# OBCv4_24.net
KiCad netlist of a schematic drawn in EAGLE
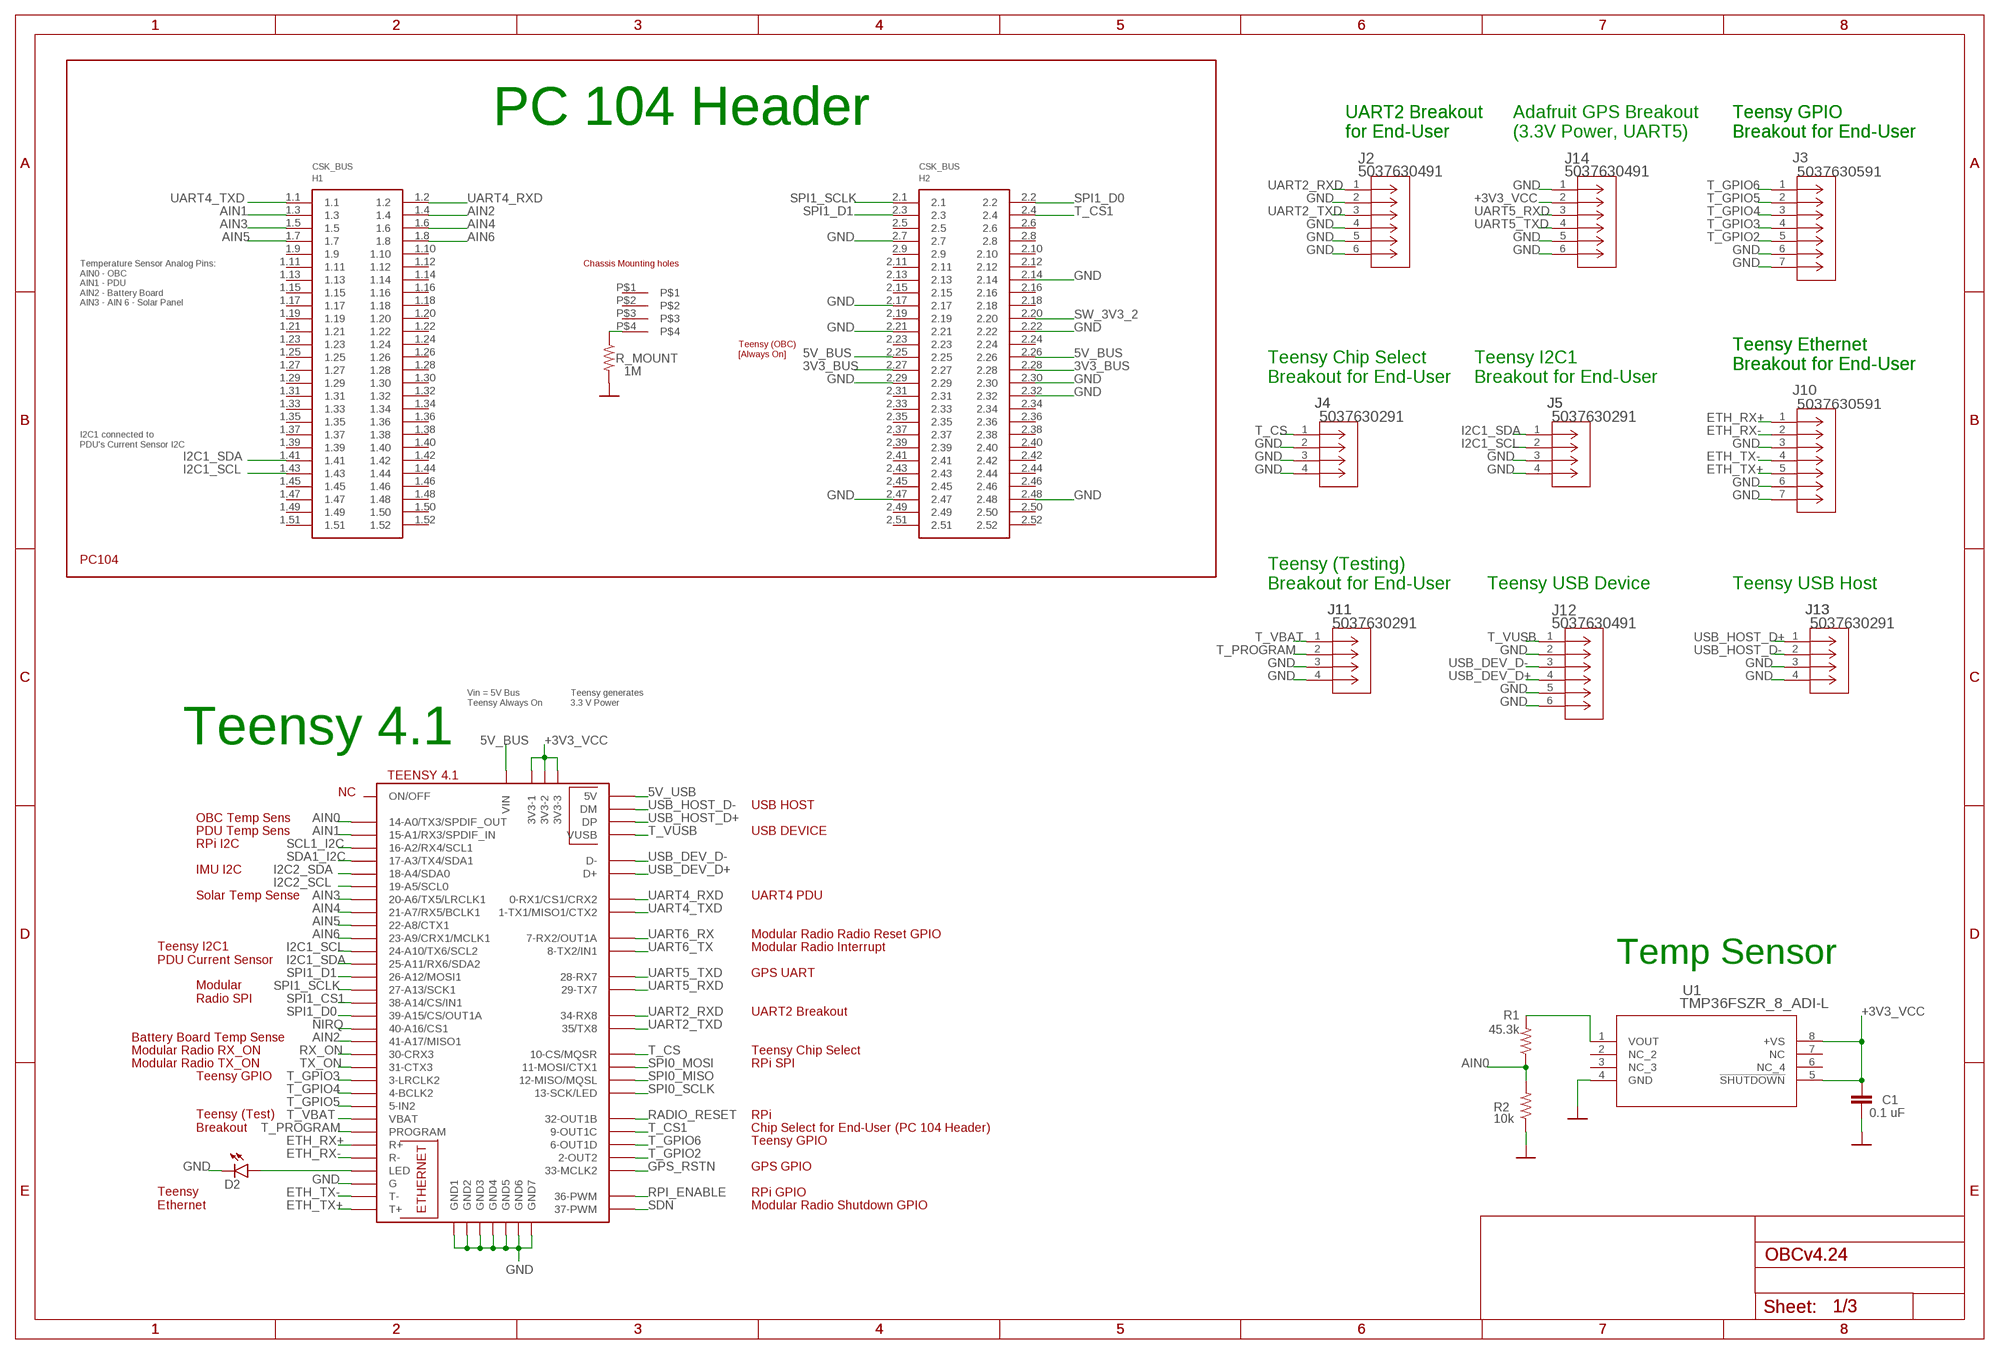
[diagram p0: schematic, sheet 1]
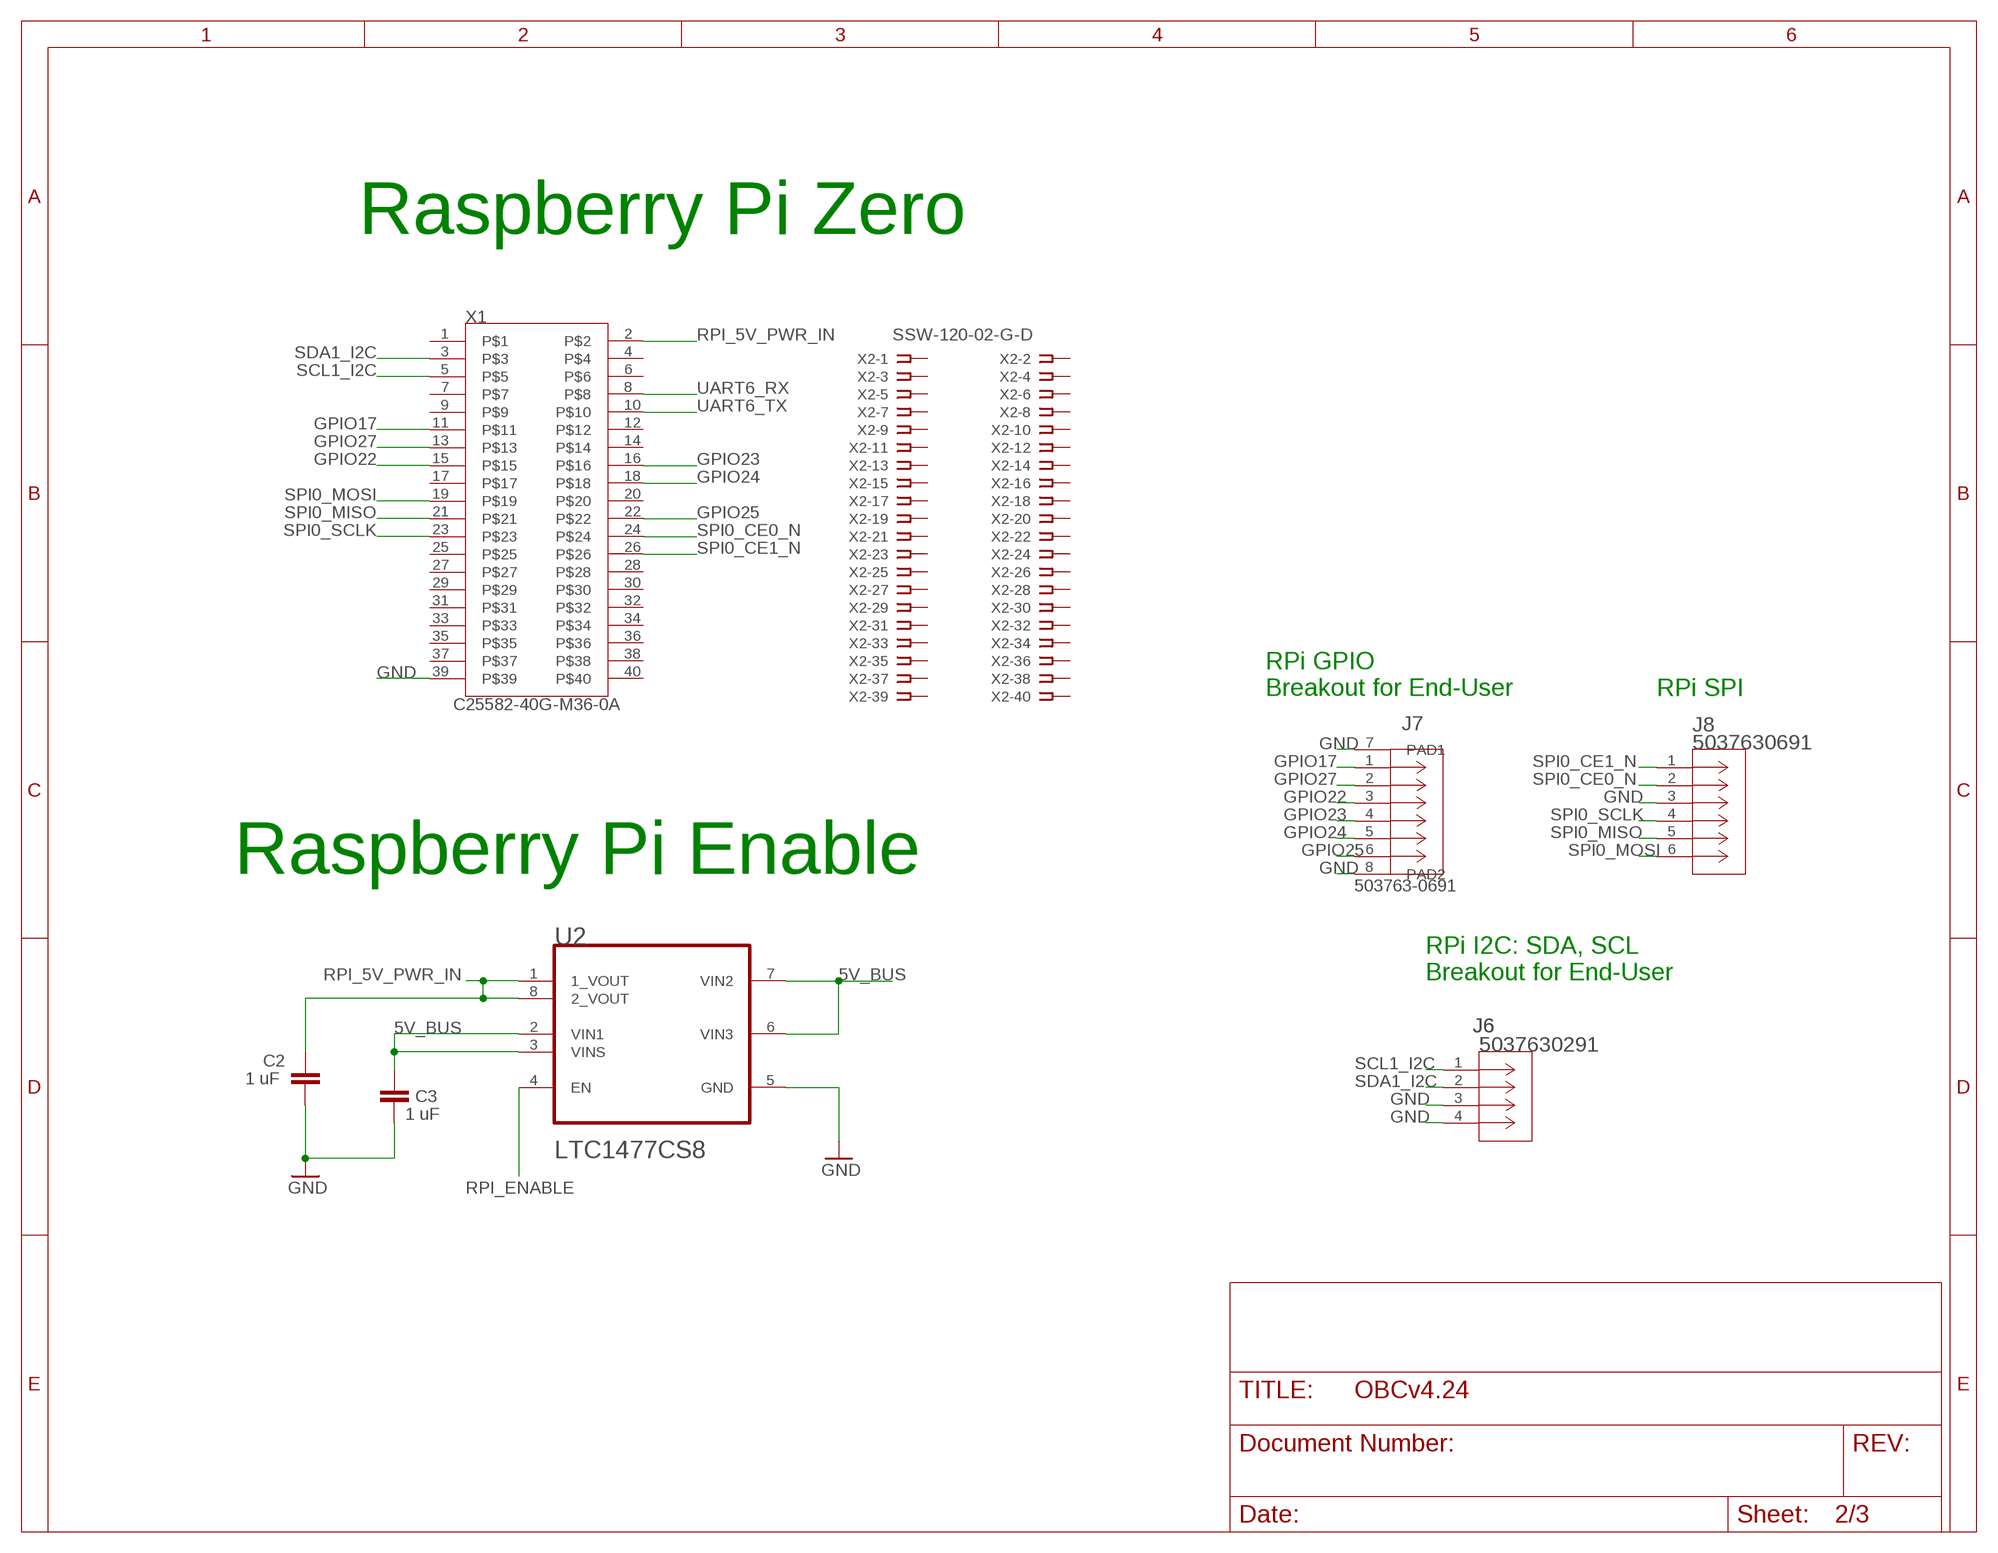
[diagram p1: schematic, sheet 2]
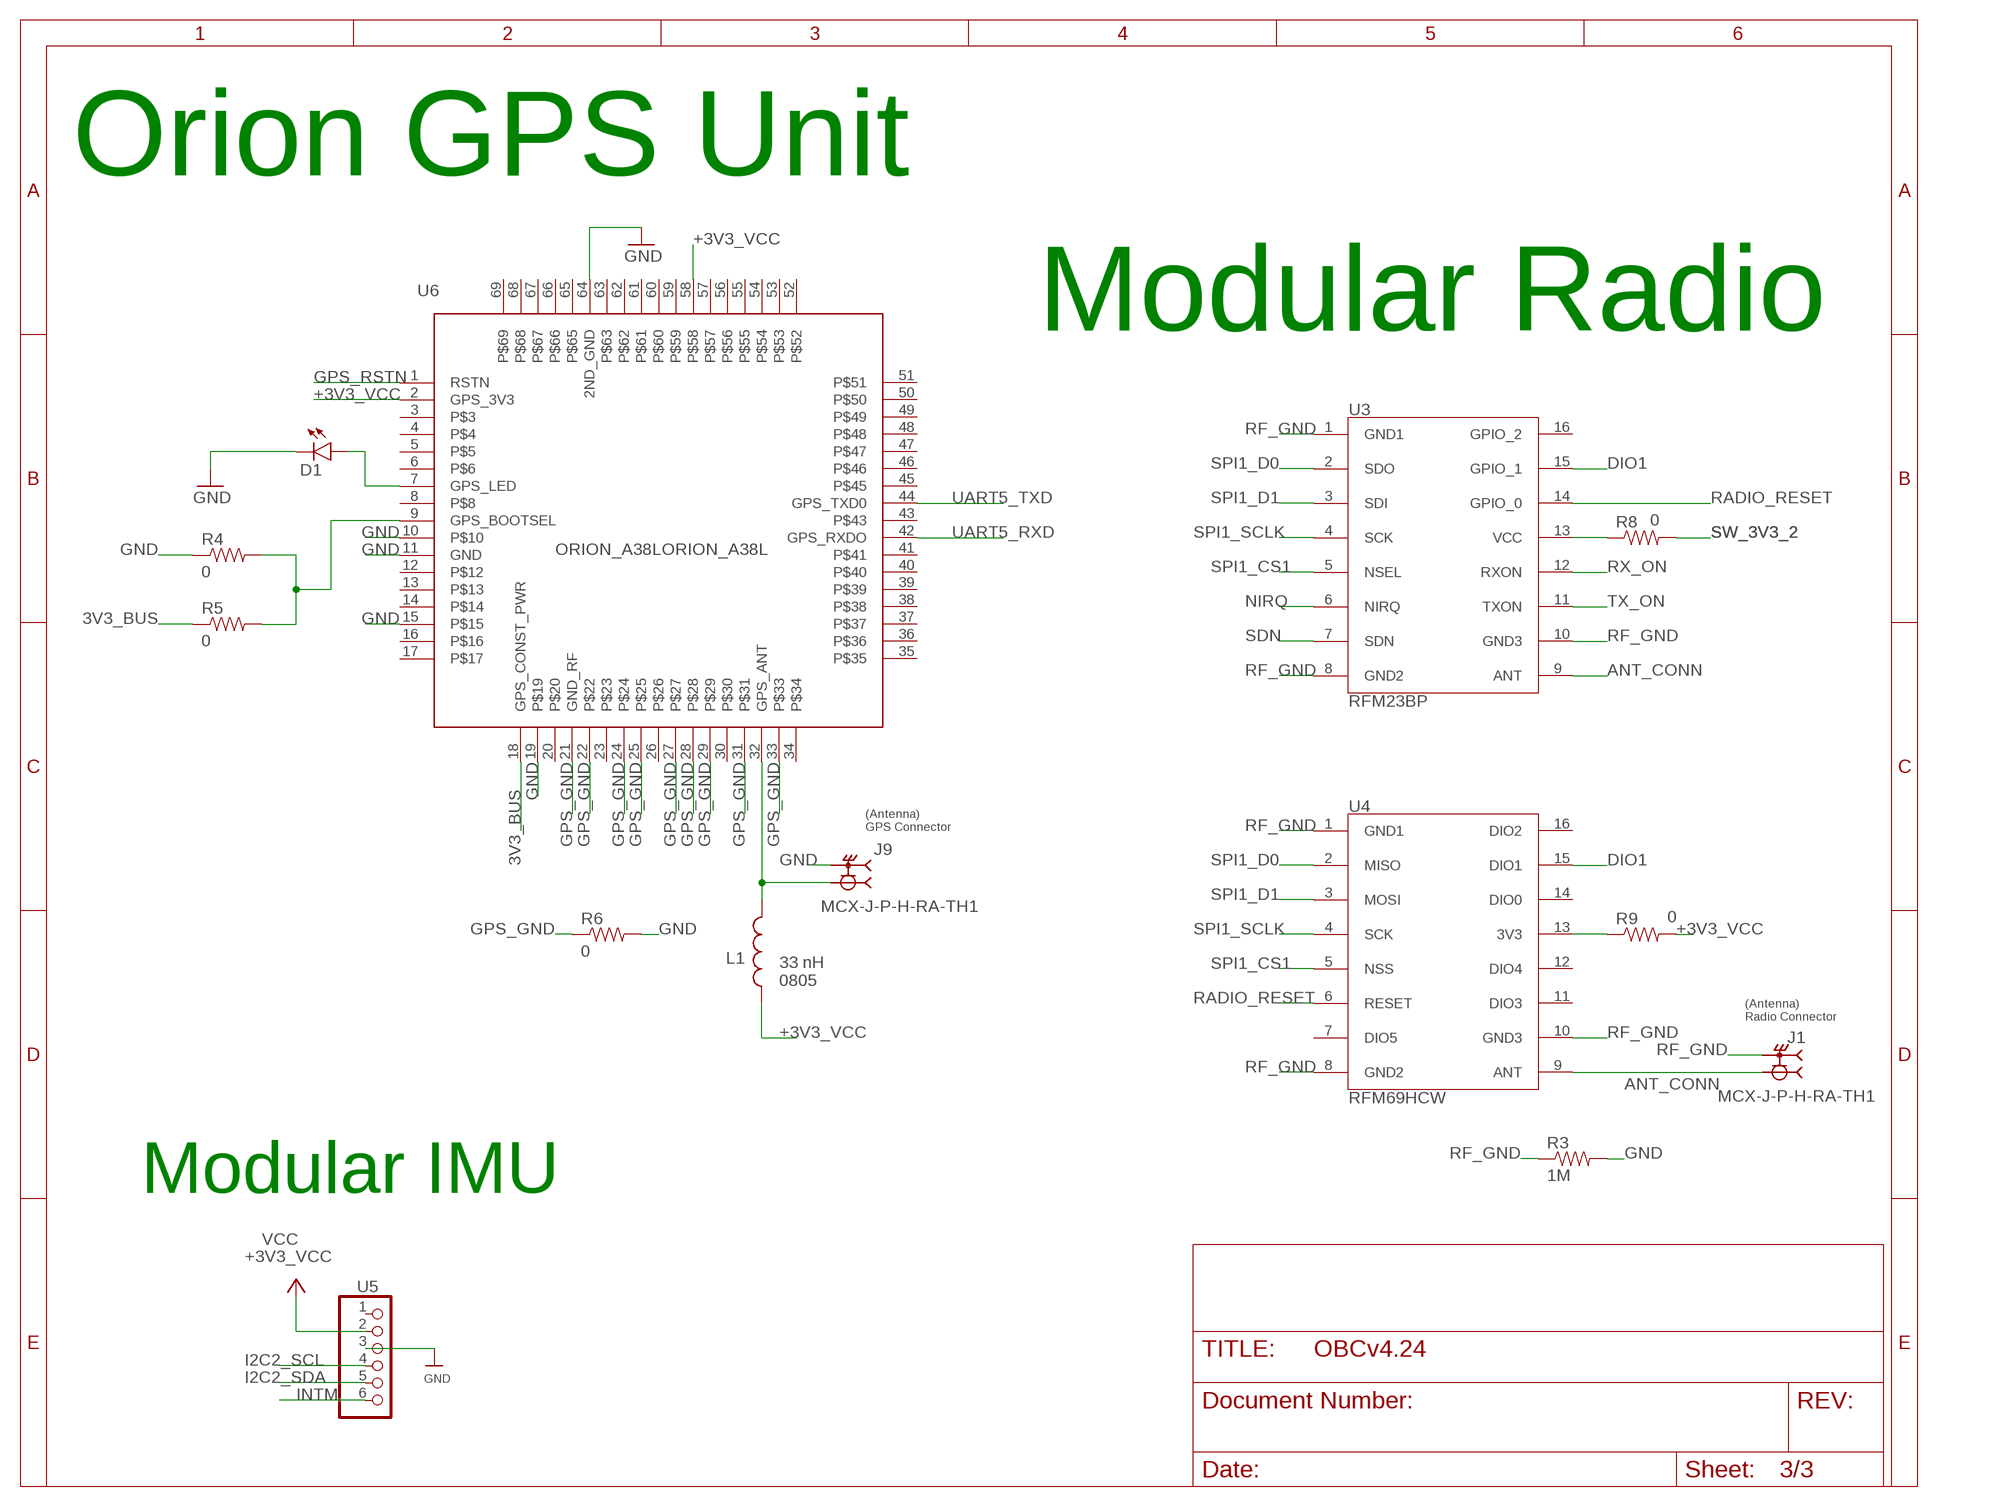
[diagram p2: schematic, sheet 3]

(export (version "E")
  (design (tool "Eeschema 10.0.6"))
  (components
    (comp (ref "D1")
      (value "LEDCHIP-LED0603")
      (footprint "eagle-import:CHIP-LED0603")
      (libsource (lib "eagle-import") (part "LEDCHIP-LED0603"))
    )
    (comp (ref "J1")
      (value "MCX-J-P-H-RA-TH1")
      (footprint "eagle-import:SAMTEC_MCX-J-P-H-RA-TH1")
      (fields (field (name "DIGI-KEY_PART_NUMBER") "SAM10607-ND") (field (name "MF") "Samtec"))
      (libsource (lib "eagle-import") (part "MCX-J-P-H-RA-TH1"))
    )
    (comp (ref "J9")
      (value "MCX-J-P-H-RA-TH1")
      (footprint "eagle-import:SAMTEC_MCX-J-P-H-RA-TH1")
      (fields (field (name "DIGI-KEY_PART_NUMBER") "SAM10607-ND") (field (name "MF") "Samtec"))
      (libsource (lib "eagle-import") (part "MCX-J-P-H-RA-TH1"))
    )
    (comp (ref "L1")
      (value "AIMC-0805-2N2S-T")
      (footprint "eagle-import:INDC2012X105N")
      (fields (field (name "DIGI-KEY_PART_NUMBER") "535-11562-1-ND") (field (name "MF") "Abracon"))
      (libsource (lib "eagle-import") (part "AIMC-0805-2N2S-T"))
    )
    (comp (ref "R3")
      (value "1M")
      (footprint "eagle-import:0805")
      (libsource (lib "eagle-import") (part "RESISTOR0805-RES"))
    )
    (comp (ref "R4")
      (value "0")
      (footprint "eagle-import:0805")
      (libsource (lib "eagle-import") (part "RESISTOR0805-RES"))
    )
    (comp (ref "R5")
      (value "0")
      (footprint "eagle-import:0805")
      (libsource (lib "eagle-import") (part "RESISTOR0805-RES"))
    )
    (comp (ref "R6")
      (value "0")
      (footprint "eagle-import:0805")
      (libsource (lib "eagle-import") (part "RESISTOR0805-RES"))
    )
    (comp (ref "R8")
      (value "0")
      (footprint "eagle-import:R2512")
      (libsource (lib "eagle-import") (part "RESISTOR2512"))
    )
    (comp (ref "R9")
      (value "0")
      (footprint "eagle-import:R2512")
      (libsource (lib "eagle-import") (part "RESISTOR2512"))
    )
    (comp (ref "U3")
      (value "RFM23BP")
      (footprint "eagle-import:RFM23BP")
      (libsource (lib "eagle-import") (part "RFM23BP"))
    )
    (comp (ref "U4")
      (value "RFM69HCW")
      (footprint "eagle-import:RFM69HCW")
      (libsource (lib "eagle-import") (part "RFM69HCW"))
    )
    (comp (ref "U5")
      (value "HEADER-1X670MIL")
      (footprint "eagle-import:1X06_ROUND_70")
      (libsource (lib "eagle-import") (part "HEADER-1X670MIL"))
    )
    (comp (ref "U6")
      (value "ORION_A38LORION_A38L")
      (footprint "eagle-import:ORION_A38L")
      (libsource (lib "eagle-import") (part "ORION_A38LORION_A38L"))
    )
    (comp (ref "C2")
      (value "1 uF")
      (footprint "eagle-import:0805")
      (libsource (lib "eagle-import") (part "CAP0805"))
    )
    (comp (ref "C3")
      (value "1 uF")
      (footprint "eagle-import:0805")
      (libsource (lib "eagle-import") (part "CAP0805"))
    )
    (comp (ref "J6")
      (value "5037630291")
      (footprint "eagle-import:CON_5037630291")
      (fields (field (name "COPYRIGHT") "Copyright (C) 2018 Accelerated Designs. All rights reserved"))
      (libsource (lib "eagle-import") (part "5037630291"))
    )
    (comp (ref "J7")
      (value "503763-0691")
      (footprint "eagle-import:CONN_503763-0691_MOL")
      (fields (field (name "COPYRIGHT") "Copyright (C) 2018 Accelerated Designs. All rights reserved"))
      (libsource (lib "eagle-import") (part "503763-0691"))
    )
    (comp (ref "J8")
      (value "5037630691")
      (footprint "eagle-import:CONN_503763-0691_MOL")
      (fields
        (field (name "MANUFACTURER_PART_NUMBER") "503763-0691")
        (field (name "COPYRIGHT") "Copyright (C) 2018 Accelerated Designs. All rights reserved")
      )
      (libsource (lib "eagle-import") (part "5037630691"))
    )
    (comp (ref "U2")
      (value "LTC1477CS8LINEAR_TECHNOLOGY_LTC1477CS8_0_2")
      (footprint "eagle-import:LINEAR_TECHNOLOGY_LTC1477CS8_2")
      (fields (field (name "MF") "Linear Technology") (field (name "MPN") "LTC1477CS8"))
      (libsource (lib "eagle-import") (part "LTC1477CS8LINEAR_TECHNOLOGY_LTC1477CS8_0_2"))
    )
    (comp (ref "X1")
      (value "C25582-40G-M36-0A")
      (footprint "eagle-import:ADAFRUIT_C25582-40G-M36-0A_0")
      (libsource (lib "eagle-import") (part "C25582-40G-M36-0A"))
    )
    (comp (ref "X2")
      (value "SSW-120-02-G-D")
      (footprint "eagle-import:SSW-120-02-G-D")
      (fields (field (name "MF") "Samtec Inc."))
      (libsource (lib "eagle-import") (part "SSW-120-02-G-D"))
    )
    (comp (ref "C1")
      (value "0.1 uF")
      (footprint "eagle-import:0805")
      (libsource (lib "eagle-import") (part "CAP0805"))
    )
    (comp (ref "D2")
      (value "LEDCHIP-LED0603")
      (footprint "eagle-import:CHIP-LED0603")
      (libsource (lib "eagle-import") (part "LEDCHIP-LED0603"))
    )
    (comp (ref "H1")
      (value "PC104_WCONN")
      (footprint "eagle-import:PC104_WCONN")
      (libsource (lib "eagle-import") (part "PC104_WCONN"))
    )
    (comp (ref "J2")
      (value "5037630491")
      (footprint "eagle-import:CON_5037630491")
      (fields (field (name "COPYRIGHT") "Copyright (C) 2018 Accelerated Designs. All rights reserved"))
      (libsource (lib "eagle-import") (part "5037630491"))
    )
    (comp (ref "J3")
      (value "5037630591")
      (footprint "eagle-import:CON_5037630591")
      (fields (field (name "COPYRIGHT") "Copyright (C) 2021 Ultra Librarian. All rights reserved."))
      (libsource (lib "eagle-import") (part "5037630591"))
    )
    (comp (ref "J4")
      (value "5037630291")
      (footprint "eagle-import:CON_5037630291")
      (fields (field (name "COPYRIGHT") "Copyright (C) 2018 Accelerated Designs. All rights reserved"))
      (libsource (lib "eagle-import") (part "5037630291"))
    )
    (comp (ref "J5")
      (value "5037630291")
      (footprint "eagle-import:CON_5037630291")
      (fields (field (name "COPYRIGHT") "Copyright (C) 2018 Accelerated Designs. All rights reserved"))
      (libsource (lib "eagle-import") (part "5037630291"))
    )
    (comp (ref "J10")
      (value "5037630591")
      (footprint "eagle-import:CON_5037630591")
      (fields (field (name "COPYRIGHT") "Copyright (C) 2021 Ultra Librarian. All rights reserved."))
      (libsource (lib "eagle-import") (part "5037630591"))
    )
    (comp (ref "J11")
      (value "5037630291")
      (footprint "eagle-import:CON_5037630291")
      (fields (field (name "COPYRIGHT") "Copyright (C) 2018 Accelerated Designs. All rights reserved"))
      (libsource (lib "eagle-import") (part "5037630291"))
    )
    (comp (ref "J12")
      (value "5037630491")
      (footprint "eagle-import:CON_5037630491")
      (fields (field (name "COPYRIGHT") "Copyright (C) 2018 Accelerated Designs. All rights reserved"))
      (libsource (lib "eagle-import") (part "5037630491"))
    )
    (comp (ref "J13")
      (value "5037630291")
      (footprint "eagle-import:CON_5037630291")
      (fields (field (name "COPYRIGHT") "Copyright (C) 2018 Accelerated Designs. All rights reserved"))
      (libsource (lib "eagle-import") (part "5037630291"))
    )
    (comp (ref "J14")
      (value "5037630491")
      (footprint "eagle-import:CON_5037630491")
      (fields (field (name "COPYRIGHT") "Copyright (C) 2018 Accelerated Designs. All rights reserved"))
      (libsource (lib "eagle-import") (part "5037630491"))
    )
    (comp (ref "R1")
      (value "45.3k")
      (footprint "eagle-import:0805")
      (libsource (lib "eagle-import") (part "RESISTOR0805-RES"))
    )
    (comp (ref "R2")
      (value "10k")
      (footprint "eagle-import:0805")
      (libsource (lib "eagle-import") (part "RESISTOR0805-RES"))
    )
    (comp (ref "R_MOUNT")
      (value "1M")
      (footprint "eagle-import:0805")
      (libsource (lib "eagle-import") (part "RESISTOR0805-RES"))
    )
    (comp (ref "U$1")
      (value "TEENSY41TEENSY")
      (footprint "eagle-import:TEENSY41")
      (libsource (lib "eagle-import") (part "TEENSY41TEENSY"))
    )
    (comp (ref "U1")
      (value "TMP36FSZR_8_ADI-L")
      (footprint "eagle-import:R_8_ADI-L")
      (fields
        (field (name "MANUFACTURER_PART_NUMBER") "TMP36FSZ")
        (field (name "COPYRIGHT") "Copyright (C) 2021 Ultra Librarian. All rights reserved.")
      )
      (libsource (lib "eagle-import") (part "TMP36FSZR_8_ADI-L"))
    )
  )
  (nets
    (net (code "1") (name "+3V3_VCC") (class "Default")
      (node (ref "C1") (pin "1") (pinfunction "1_1") (pintype "passive"))
      (node (ref "J14") (pin "2") (pinfunction "2_2") (pintype "passive"))
      (node (ref "L1") (pin "1") (pinfunction "1_1") (pintype "passive"))
      (node (ref "R9") (pin "2") (pinfunction "2_2") (pintype "passive"))
      (node (ref "U$1") (pin "3V3-1") (pinfunction "3V3-1_3V3-1") (pintype "bidirectional"))
      (node (ref "U$1") (pin "3V3-2") (pinfunction "3V3-2_3V3-2") (pintype "bidirectional"))
      (node (ref "U$1") (pin "3V3-3") (pinfunction "3V3-3_3V3-3") (pintype "bidirectional"))
      (node (ref "U1") (pin "5") (pinfunction "~{SHUTDOWN}_5") (pintype "passive"))
      (node (ref "U1") (pin "8") (pinfunction "+VS_8") (pintype "power_in"))
      (node (ref "U5") (pin "2") (pinfunction "2_2") (pintype "passive"))
      (node (ref "U6") (pin "2") (pinfunction "GPS_3V3_2") (pintype "bidirectional"))
      (node (ref "U6") (pin "58") (pinfunction "P$58_58") (pintype "bidirectional"))
    )
    (net (code "2") (name "3V3_BUS") (class "Default")
      (node (ref "H1") (pin "2.27") (pinfunction "2.27_2.27") (pintype "bidirectional"))
      (node (ref "H1") (pin "2.28") (pinfunction "2.28_2.28") (pintype "bidirectional"))
      (node (ref "R5") (pin "1") (pinfunction "1_1") (pintype "passive"))
      (node (ref "U6") (pin "18") (pinfunction "GPS_CONST_PWR_18") (pintype "bidirectional"))
    )
    (net (code "3") (name "5V_BUS") (class "Default")
      (node (ref "C3") (pin "1") (pinfunction "1_1") (pintype "passive"))
      (node (ref "H1") (pin "2.25") (pinfunction "2.25_2.25") (pintype "bidirectional"))
      (node (ref "H1") (pin "2.26") (pinfunction "2.26_2.26") (pintype "bidirectional"))
      (node (ref "U$1") (pin "VIN") (pinfunction "VIN_VIN") (pintype "bidirectional"))
      (node (ref "U2") (pin "2") (pinfunction "VIN1_2") (pintype "power_in"))
      (node (ref "U2") (pin "3") (pinfunction "VINS_3") (pintype "power_in"))
      (node (ref "U2") (pin "6") (pinfunction "VIN3_6") (pintype "power_in"))
      (node (ref "U2") (pin "7") (pinfunction "VIN2_7") (pintype "power_in"))
    )
    (net (code "4") (name "5V_USB") (class "Default")
      (node (ref "U$1") (pin "+5V") (pinfunction "5V_+5V") (pintype "bidirectional"))
    )
    (net (code "5") (name "AIN0") (class "Default")
      (node (ref "R1") (pin "1") (pinfunction "1_1") (pintype "passive"))
      (node (ref "R2") (pin "2") (pinfunction "2_2") (pintype "passive"))
      (node (ref "U$1") (pin "14-A0/TX3/SPDIF_OUT") (pinfunction "14-A0/TX3/SPDIF_OUT_14-A0/TX3/SPDIF_OUT") (pintype "bidirectional"))
    )
    (net (code "6") (name "AIN1") (class "Default")
      (node (ref "H1") (pin "1.3") (pinfunction "1.3_1.3") (pintype "bidirectional"))
      (node (ref "U$1") (pin "15-A1/RX3/SPDIF_IN") (pinfunction "15-A1/RX3/SPDIF_IN_15-A1/RX3/SPDIF_IN") (pintype "bidirectional"))
    )
    (net (code "7") (name "AIN2") (class "Default")
      (node (ref "H1") (pin "1.4") (pinfunction "1.4_1.4") (pintype "bidirectional"))
      (node (ref "U$1") (pin "41-A17/MISO1") (pinfunction "41-A17/MISO1_41-A17/MISO1") (pintype "bidirectional"))
    )
    (net (code "8") (name "AIN3") (class "Default")
      (node (ref "H1") (pin "1.5") (pinfunction "1.5_1.5") (pintype "bidirectional"))
      (node (ref "U$1") (pin "20-A6/TX5/LRCLK1") (pinfunction "20-A6/TX5/LRCLK1_20-A6/TX5/LRCLK1") (pintype "bidirectional"))
    )
    (net (code "9") (name "AIN4") (class "Default")
      (node (ref "H1") (pin "1.6") (pinfunction "1.6_1.6") (pintype "bidirectional"))
      (node (ref "U$1") (pin "21-A7/RX5/BCLK1") (pinfunction "21-A7/RX5/BCLK1_21-A7/RX5/BCLK1") (pintype "bidirectional"))
    )
    (net (code "10") (name "AIN5") (class "Default")
      (node (ref "H1") (pin "1.7") (pinfunction "1.7_1.7") (pintype "bidirectional"))
      (node (ref "U$1") (pin "22-A8/CTX1") (pinfunction "22-A8/CTX1_22-A8/CTX1") (pintype "bidirectional"))
    )
    (net (code "11") (name "AIN6") (class "Default")
      (node (ref "H1") (pin "1.8") (pinfunction "1.8_1.8") (pintype "bidirectional"))
      (node (ref "U$1") (pin "23-A9/CRX1/MCLK1") (pinfunction "23-A9/CRX1/MCLK1_23-A9/CRX1/MCLK1") (pintype "bidirectional"))
    )
    (net (code "12") (name "ANT_CONN") (class "Default")
      (node (ref "J1") (pin "1") (pinfunction "1_1") (pintype "passive"))
      (node (ref "U3") (pin "9") (pinfunction "ANT_9") (pintype "bidirectional"))
      (node (ref "U4") (pin "9") (pinfunction "ANT_9") (pintype "bidirectional"))
    )
    (net (code "13") (name "DIO1") (class "Default")
      (node (ref "U3") (pin "15") (pinfunction "GPIO_1_15") (pintype "bidirectional"))
      (node (ref "U4") (pin "15") (pinfunction "DIO1_15") (pintype "bidirectional"))
    )
    (net (code "14") (name "ETH_RX+") (class "Default")
      (node (ref "J10") (pin "1") (pinfunction "1_1") (pintype "passive"))
      (node (ref "U$1") (pin "R+") (pinfunction "R+_R+") (pintype "bidirectional"))
    )
    (net (code "15") (name "ETH_RX-") (class "Default")
      (node (ref "J10") (pin "2") (pinfunction "2_2") (pintype "passive"))
      (node (ref "U$1") (pin "R-") (pinfunction "R-_R-") (pintype "bidirectional"))
    )
    (net (code "16") (name "ETH_TX+") (class "Default")
      (node (ref "J10") (pin "5") (pinfunction "5_5") (pintype "passive"))
      (node (ref "U$1") (pin "T+") (pinfunction "T+_T+") (pintype "bidirectional"))
    )
    (net (code "17") (name "ETH_TX-") (class "Default")
      (node (ref "J10") (pin "4") (pinfunction "4_4") (pintype "passive"))
      (node (ref "U$1") (pin "T-") (pinfunction "T-_T-") (pintype "bidirectional"))
    )
    (net (code "18") (name "GND") (class "Default")
      (node (ref "C1") (pin "2") (pinfunction "2_2") (pintype "passive"))
      (node (ref "C2") (pin "2") (pinfunction "2_2") (pintype "passive"))
      (node (ref "C3") (pin "2") (pinfunction "2_2") (pintype "passive"))
      (node (ref "D1") (pin "C") (pinfunction "C_C") (pintype "passive"))
      (node (ref "D2") (pin "C") (pinfunction "C_C") (pintype "passive"))
      (node (ref "H1") (pin "2.14") (pinfunction "2.14_2.14") (pintype "bidirectional"))
      (node (ref "H1") (pin "2.17") (pinfunction "2.17_2.17") (pintype "bidirectional"))
      (node (ref "H1") (pin "2.21") (pinfunction "2.21_2.21") (pintype "bidirectional"))
      (node (ref "H1") (pin "2.22") (pinfunction "2.22_2.22") (pintype "bidirectional"))
      (node (ref "H1") (pin "2.29") (pinfunction "2.29_2.29") (pintype "bidirectional"))
      (node (ref "H1") (pin "2.30") (pinfunction "2.30_2.30") (pintype "bidirectional"))
      (node (ref "H1") (pin "2.32") (pinfunction "2.32_2.32") (pintype "bidirectional"))
      (node (ref "H1") (pin "2.47") (pinfunction "2.47_2.47") (pintype "bidirectional"))
      (node (ref "H1") (pin "2.48") (pinfunction "2.48_2.48") (pintype "bidirectional"))
      (node (ref "H1") (pin "2.7") (pinfunction "2.7_2.7") (pintype "bidirectional"))
      (node (ref "J10") (pin "3") (pinfunction "3_3") (pintype "passive"))
      (node (ref "J10") (pin "6") (pinfunction "6_6") (pintype "passive"))
      (node (ref "J10") (pin "7") (pinfunction "7_7") (pintype "passive"))
      (node (ref "J11") (pin "3") (pinfunction "3_3") (pintype "passive"))
      (node (ref "J11") (pin "4") (pinfunction "4_4") (pintype "passive"))
      (node (ref "J12") (pin "2") (pinfunction "2_2") (pintype "passive"))
      (node (ref "J12") (pin "5") (pinfunction "5_5") (pintype "passive"))
      (node (ref "J12") (pin "6") (pinfunction "6_6") (pintype "passive"))
      (node (ref "J13") (pin "3") (pinfunction "3_3") (pintype "passive"))
      (node (ref "J13") (pin "4") (pinfunction "4_4") (pintype "passive"))
      (node (ref "J14") (pin "1") (pinfunction "1_1") (pintype "passive"))
      (node (ref "J14") (pin "5") (pinfunction "5_5") (pintype "passive"))
      (node (ref "J14") (pin "6") (pinfunction "6_6") (pintype "passive"))
      (node (ref "J2") (pin "2") (pinfunction "2_2") (pintype "passive"))
      (node (ref "J2") (pin "4") (pinfunction "4_4") (pintype "passive"))
      (node (ref "J2") (pin "5") (pinfunction "5_5") (pintype "passive"))
      (node (ref "J2") (pin "6") (pinfunction "6_6") (pintype "passive"))
      (node (ref "J3") (pin "6") (pinfunction "6_6") (pintype "passive"))
      (node (ref "J3") (pin "7") (pinfunction "7_7") (pintype "passive"))
      (node (ref "J4") (pin "2") (pinfunction "2_2") (pintype "passive"))
      (node (ref "J4") (pin "3") (pinfunction "3_3") (pintype "passive"))
      (node (ref "J4") (pin "4") (pinfunction "4_4") (pintype "passive"))
      (node (ref "J5") (pin "3") (pinfunction "3_3") (pintype "passive"))
      (node (ref "J5") (pin "4") (pinfunction "4_4") (pintype "passive"))
      (node (ref "J6") (pin "3") (pinfunction "3_3") (pintype "passive"))
      (node (ref "J6") (pin "4") (pinfunction "4_4") (pintype "passive"))
      (node (ref "J7") (pin "7") (pinfunction "PAD1_7") (pintype "bidirectional"))
      (node (ref "J7") (pin "8") (pinfunction "PAD2_8") (pintype "bidirectional"))
      (node (ref "J8") (pin "3") (pinfunction "3_3") (pintype "passive"))
      (node (ref "J9") (pin "S1") (pinfunction "2_S1") (pintype "passive"))
      (node (ref "J9") (pin "S2") (pinfunction "2_S2") (pintype "passive"))
      (node (ref "J9") (pin "S3") (pinfunction "2_S3") (pintype "passive"))
      (node (ref "J9") (pin "S4") (pinfunction "2_S4") (pintype "passive"))
      (node (ref "R2") (pin "1") (pinfunction "1_1") (pintype "passive"))
      (node (ref "R3") (pin "2") (pinfunction "2_2") (pintype "passive"))
      (node (ref "R4") (pin "1") (pinfunction "1_1") (pintype "passive"))
      (node (ref "R6") (pin "2") (pinfunction "2_2") (pintype "passive"))
      (node (ref "R_MOUNT") (pin "2") (pinfunction "2_2") (pintype "passive"))
      (node (ref "U$1") (pin "G") (pinfunction "G_G") (pintype "bidirectional"))
      (node (ref "U$1") (pin "GND") (pinfunction "GND7_GND") (pintype "bidirectional"))
      (node (ref "U$1") (pin "GND1") (pinfunction "GND1_GND1") (pintype "bidirectional"))
      (node (ref "U$1") (pin "GND2") (pinfunction "GND2_GND2") (pintype "bidirectional"))
      (node (ref "U$1") (pin "GND3") (pinfunction "GND3_GND3") (pintype "bidirectional"))
      (node (ref "U$1") (pin "GND4") (pinfunction "GND4_GND4") (pintype "bidirectional"))
      (node (ref "U$1") (pin "GND5") (pinfunction "GND5_GND5") (pintype "bidirectional"))
      (node (ref "U$1") (pin "GND6") (pinfunction "GND6_GND6") (pintype "bidirectional"))
      (node (ref "U1") (pin "4") (pinfunction "GND_4") (pintype "passive"))
      (node (ref "U2") (pin "5") (pinfunction "GND_5") (pintype "power_in"))
      (node (ref "U5") (pin "3") (pinfunction "3_3") (pintype "passive"))
      (node (ref "U6") (pin "10") (pinfunction "P$10_10") (pintype "bidirectional"))
      (node (ref "U6") (pin "11") (pinfunction "GND_11") (pintype "bidirectional"))
      (node (ref "U6") (pin "15") (pinfunction "P$15_15") (pintype "bidirectional"))
      (node (ref "U6") (pin "19") (pinfunction "P$19_19") (pintype "bidirectional"))
      (node (ref "U6") (pin "64") (pinfunction "2ND_GND_64") (pintype "bidirectional"))
      (node (ref "X1") (pin "39") (pinfunction "P$39_39") (pintype "bidirectional"))
    )
    (net (code "19") (name "GPIO17") (class "Default")
      (node (ref "J7") (pin "1") (pinfunction "1_1") (pintype "passive"))
      (node (ref "X1") (pin "11") (pinfunction "P$11_11") (pintype "bidirectional"))
    )
    (net (code "20") (name "GPIO22") (class "Default")
      (node (ref "J7") (pin "3") (pinfunction "3_3") (pintype "passive"))
      (node (ref "X1") (pin "15") (pinfunction "P$15_15") (pintype "bidirectional"))
    )
    (net (code "21") (name "GPIO23") (class "Default")
      (node (ref "J7") (pin "4") (pinfunction "4_4") (pintype "passive"))
      (node (ref "X1") (pin "16") (pinfunction "P$16_16") (pintype "bidirectional"))
    )
    (net (code "22") (name "GPIO24") (class "Default")
      (node (ref "J7") (pin "5") (pinfunction "5_5") (pintype "passive"))
      (node (ref "X1") (pin "18") (pinfunction "P$18_18") (pintype "bidirectional"))
    )
    (net (code "23") (name "GPIO25") (class "Default")
      (node (ref "J7") (pin "6") (pinfunction "6_6") (pintype "passive"))
      (node (ref "X1") (pin "22") (pinfunction "P$22_22") (pintype "bidirectional"))
    )
    (net (code "24") (name "GPIO27") (class "Default")
      (node (ref "J7") (pin "2") (pinfunction "2_2") (pintype "passive"))
      (node (ref "X1") (pin "13") (pinfunction "P$13_13") (pintype "bidirectional"))
    )
    (net (code "25") (name "GPS_GND") (class "Default")
      (node (ref "R6") (pin "1") (pinfunction "1_1") (pintype "passive"))
      (node (ref "U6") (pin "21") (pinfunction "GND_RF_21") (pintype "bidirectional"))
      (node (ref "U6") (pin "22") (pinfunction "P$22_22") (pintype "bidirectional"))
      (node (ref "U6") (pin "24") (pinfunction "P$24_24") (pintype "bidirectional"))
      (node (ref "U6") (pin "25") (pinfunction "P$25_25") (pintype "bidirectional"))
      (node (ref "U6") (pin "27") (pinfunction "P$27_27") (pintype "bidirectional"))
      (node (ref "U6") (pin "28") (pinfunction "P$28_28") (pintype "bidirectional"))
      (node (ref "U6") (pin "29") (pinfunction "P$29_29") (pintype "bidirectional"))
      (node (ref "U6") (pin "31") (pinfunction "P$31_31") (pintype "bidirectional"))
      (node (ref "U6") (pin "33") (pinfunction "P$33_33") (pintype "bidirectional"))
    )
    (net (code "26") (name "GPS_RSTN") (class "Default")
      (node (ref "U$1") (pin "33-MCLK2") (pinfunction "33-MCLK2_33-MCLK2") (pintype "bidirectional"))
      (node (ref "U6") (pin "1") (pinfunction "RSTN_1") (pintype "bidirectional"))
    )
    (net (code "27") (name "I2C1_SCL") (class "Default")
      (node (ref "H1") (pin "1.43") (pinfunction "1.43_1.43") (pintype "bidirectional"))
      (node (ref "J5") (pin "2") (pinfunction "2_2") (pintype "passive"))
      (node (ref "U$1") (pin "24-A10/TX6/SCL2") (pinfunction "24-A10/TX6/SCL2_24-A10/TX6/SCL2") (pintype "bidirectional"))
    )
    (net (code "28") (name "I2C1_SDA") (class "Default")
      (node (ref "H1") (pin "1.41") (pinfunction "1.41_1.41") (pintype "bidirectional"))
      (node (ref "J5") (pin "1") (pinfunction "1_1") (pintype "passive"))
      (node (ref "U$1") (pin "25-A11/RX6/SDA2") (pinfunction "25-A11/RX6/SDA2_25-A11/RX6/SDA2") (pintype "bidirectional"))
    )
    (net (code "29") (name "I2C2_SCL") (class "Default")
      (node (ref "U$1") (pin "19-A5/SCL0") (pinfunction "19-A5/SCL0_19-A5/SCL0") (pintype "bidirectional"))
      (node (ref "U5") (pin "4") (pinfunction "4_4") (pintype "passive"))
    )
    (net (code "30") (name "I2C2_SDA") (class "Default")
      (node (ref "U$1") (pin "18-A4/SDA0") (pinfunction "18-A4/SDA0_18-A4/SDA0") (pintype "bidirectional"))
      (node (ref "U5") (pin "5") (pinfunction "5_5") (pintype "passive"))
    )
    (net (code "31") (name "INTM") (class "Default")
      (node (ref "U5") (pin "6") (pinfunction "6_6") (pintype "passive"))
    )
    (net (code "32") (name "NIRQ") (class "Default")
      (node (ref "U$1") (pin "40-A16/CS1") (pinfunction "40-A16/CS1_40-A16/CS1") (pintype "bidirectional"))
      (node (ref "U3") (pin "6") (pinfunction "NIRQ_6") (pintype "bidirectional"))
    )
    (net (code "33") (name "Net-(D2-PadA)") (class "Default")
      (node (ref "D2") (pin "A") (pinfunction "A_A") (pintype "passive"))
      (node (ref "U$1") (pin "LED") (pinfunction "LED_LED") (pintype "bidirectional"))
    )
    (net (code "34") (name "Net-(H1-PadP$4)") (class "Default")
      (node (ref "H1") (pin "P$4") (pinfunction "P$4_P$4") (pintype "bidirectional"))
      (node (ref "R_MOUNT") (pin "1") (pinfunction "1_1") (pintype "passive"))
    )
    (net (code "35") (name "Net-(U1-VOUT)") (class "Default")
      (node (ref "R1") (pin "2") (pinfunction "2_2") (pintype "passive"))
      (node (ref "U1") (pin "1") (pinfunction "VOUT_1") (pintype "output"))
    )
    (net (code "36") (name "Net-(U3-VCC)") (class "Default")
      (node (ref "R8") (pin "1") (pinfunction "1_1") (pintype "passive"))
      (node (ref "U3") (pin "13") (pinfunction "VCC_13") (pintype "bidirectional"))
    )
    (net (code "37") (name "Net-(U4-3V3)") (class "Default")
      (node (ref "R9") (pin "1") (pinfunction "1_1") (pintype "passive"))
      (node (ref "U4") (pin "13") (pinfunction "3V3_13") (pintype "bidirectional"))
    )
    (net (code "38") (name "Net-(U6-GPS_ANT)") (class "Default")
      (node (ref "J9") (pin "1") (pinfunction "1_1") (pintype "passive"))
      (node (ref "L1") (pin "2") (pinfunction "2_2") (pintype "passive"))
      (node (ref "U6") (pin "32") (pinfunction "GPS_ANT_32") (pintype "bidirectional"))
    )
    (net (code "39") (name "Net-(U6-GPS_BOOTSEL)") (class "Default")
      (node (ref "R4") (pin "2") (pinfunction "2_2") (pintype "passive"))
      (node (ref "R5") (pin "2") (pinfunction "2_2") (pintype "passive"))
      (node (ref "U6") (pin "9") (pinfunction "GPS_BOOTSEL_9") (pintype "bidirectional"))
    )
    (net (code "40") (name "Net-(U6-GPS_LED)") (class "Default")
      (node (ref "D1") (pin "A") (pinfunction "A_A") (pintype "passive"))
      (node (ref "U6") (pin "7") (pinfunction "GPS_LED_7") (pintype "bidirectional"))
    )
    (net (code "41") (name "RADIO_RESET") (class "Default")
      (node (ref "U$1") (pin "32-OUT1B") (pinfunction "32-OUT1B_32-OUT1B") (pintype "bidirectional"))
      (node (ref "U3") (pin "14") (pinfunction "GPIO_0_14") (pintype "bidirectional"))
      (node (ref "U4") (pin "6") (pinfunction "RESET_6") (pintype "bidirectional"))
    )
    (net (code "42") (name "RF_GND") (class "Default")
      (node (ref "J1") (pin "S1") (pinfunction "2_S1") (pintype "passive"))
      (node (ref "J1") (pin "S2") (pinfunction "2_S2") (pintype "passive"))
      (node (ref "J1") (pin "S3") (pinfunction "2_S3") (pintype "passive"))
      (node (ref "J1") (pin "S4") (pinfunction "2_S4") (pintype "passive"))
      (node (ref "R3") (pin "1") (pinfunction "1_1") (pintype "passive"))
      (node (ref "U3") (pin "1") (pinfunction "GND1_1") (pintype "bidirectional"))
      (node (ref "U3") (pin "10") (pinfunction "GND3_10") (pintype "bidirectional"))
      (node (ref "U3") (pin "8") (pinfunction "GND2_8") (pintype "bidirectional"))
      (node (ref "U4") (pin "1") (pinfunction "GND1_1") (pintype "bidirectional"))
      (node (ref "U4") (pin "10") (pinfunction "GND3_10") (pintype "bidirectional"))
      (node (ref "U4") (pin "8") (pinfunction "GND2_8") (pintype "bidirectional"))
    )
    (net (code "43") (name "RPI_5V_PWR_IN") (class "Default")
      (node (ref "C2") (pin "1") (pinfunction "1_1") (pintype "passive"))
      (node (ref "U2") (pin "1") (pinfunction "1_VOUT_1") (pintype "power_in"))
      (node (ref "U2") (pin "8") (pinfunction "2_VOUT_8") (pintype "power_in"))
      (node (ref "X1") (pin "2") (pinfunction "P$2_2") (pintype "bidirectional"))
    )
    (net (code "44") (name "RPI_ENABLE") (class "Default")
      (node (ref "U$1") (pin "36-PWM") (pinfunction "36-PWM_36-PWM") (pintype "bidirectional"))
      (node (ref "U2") (pin "4") (pinfunction "EN_4") (pintype "input"))
    )
    (net (code "45") (name "RX_ON") (class "Default")
      (node (ref "U$1") (pin "30-CRX3") (pinfunction "30-CRX3_30-CRX3") (pintype "bidirectional"))
      (node (ref "U3") (pin "12") (pinfunction "RXON_12") (pintype "bidirectional"))
    )
    (net (code "46") (name "SCL1_I2C") (class "Default")
      (node (ref "J6") (pin "1") (pinfunction "1_1") (pintype "passive"))
      (node (ref "U$1") (pin "16-A2/RX4/SCL1") (pinfunction "16-A2/RX4/SCL1_16-A2/RX4/SCL1") (pintype "bidirectional"))
      (node (ref "X1") (pin "5") (pinfunction "P$5_5") (pintype "bidirectional"))
    )
    (net (code "47") (name "SDA1_I2C") (class "Default")
      (node (ref "J6") (pin "2") (pinfunction "2_2") (pintype "passive"))
      (node (ref "U$1") (pin "17-A3/TX4/SDA1") (pinfunction "17-A3/TX4/SDA1_17-A3/TX4/SDA1") (pintype "bidirectional"))
      (node (ref "X1") (pin "3") (pinfunction "P$3_3") (pintype "bidirectional"))
    )
    (net (code "48") (name "SDN") (class "Default")
      (node (ref "U$1") (pin "37-PWM") (pinfunction "37-PWM_37-PWM") (pintype "bidirectional"))
      (node (ref "U3") (pin "7") (pinfunction "SDN_7") (pintype "bidirectional"))
    )
    (net (code "49") (name "SPI0_CE0_N") (class "Default")
      (node (ref "J8") (pin "2") (pinfunction "2_2") (pintype "passive"))
      (node (ref "X1") (pin "24") (pinfunction "P$24_24") (pintype "bidirectional"))
    )
    (net (code "50") (name "SPI0_CE1_N") (class "Default")
      (node (ref "J8") (pin "1") (pinfunction "1_1") (pintype "passive"))
      (node (ref "X1") (pin "26") (pinfunction "P$26_26") (pintype "bidirectional"))
    )
    (net (code "51") (name "SPI0_MISO") (class "Default")
      (node (ref "J8") (pin "5") (pinfunction "5_5") (pintype "passive"))
      (node (ref "U$1") (pin "12-MISO/MQSL") (pinfunction "12-MISO/MQSL_12-MISO/MQSL") (pintype "bidirectional"))
      (node (ref "X1") (pin "21") (pinfunction "P$21_21") (pintype "bidirectional"))
    )
    (net (code "52") (name "SPI0_MOSI") (class "Default")
      (node (ref "J8") (pin "6") (pinfunction "6_6") (pintype "passive"))
      (node (ref "U$1") (pin "11-MOSI/CTX1") (pinfunction "11-MOSI/CTX1_11-MOSI/CTX1") (pintype "bidirectional"))
      (node (ref "X1") (pin "19") (pinfunction "P$19_19") (pintype "bidirectional"))
    )
    (net (code "53") (name "SPI0_SCLK") (class "Default")
      (node (ref "J8") (pin "4") (pinfunction "4_4") (pintype "passive"))
      (node (ref "U$1") (pin "13-SCK/LED") (pinfunction "13-SCK/LED_13-SCK/LED") (pintype "bidirectional"))
      (node (ref "X1") (pin "23") (pinfunction "P$23_23") (pintype "bidirectional"))
    )
    (net (code "54") (name "SPI1_CS1") (class "Default")
      (node (ref "U$1") (pin "38-A14/CS/IN1") (pinfunction "38-A14/CS/IN1_38-A14/CS/IN1") (pintype "bidirectional"))
      (node (ref "U3") (pin "5") (pinfunction "NSEL_5") (pintype "bidirectional"))
      (node (ref "U4") (pin "5") (pinfunction "NSS_5") (pintype "bidirectional"))
    )
    (net (code "55") (name "SPI1_D0") (class "Default")
      (node (ref "H1") (pin "2.2") (pinfunction "2.2_2.2") (pintype "bidirectional"))
      (node (ref "U$1") (pin "39-A15/CS/OUT1A") (pinfunction "39-A15/CS/OUT1A_39-A15/CS/OUT1A") (pintype "bidirectional"))
      (node (ref "U3") (pin "2") (pinfunction "SDO_2") (pintype "bidirectional"))
      (node (ref "U4") (pin "2") (pinfunction "MISO_2") (pintype "bidirectional"))
    )
    (net (code "56") (name "SPI1_D1") (class "Default")
      (node (ref "H1") (pin "2.3") (pinfunction "2.3_2.3") (pintype "bidirectional"))
      (node (ref "U$1") (pin "26-A12/MOSI1") (pinfunction "26-A12/MOSI1_26-A12/MOSI1") (pintype "bidirectional"))
      (node (ref "U3") (pin "3") (pinfunction "SDI_3") (pintype "bidirectional"))
      (node (ref "U4") (pin "3") (pinfunction "MOSI_3") (pintype "bidirectional"))
    )
    (net (code "57") (name "SPI1_SCLK") (class "Default")
      (node (ref "H1") (pin "2.1") (pinfunction "2.1_2.1") (pintype "bidirectional"))
      (node (ref "U$1") (pin "27-A13/SCK1") (pinfunction "27-A13/SCK1_27-A13/SCK1") (pintype "bidirectional"))
      (node (ref "U3") (pin "4") (pinfunction "SCK_4") (pintype "bidirectional"))
      (node (ref "U4") (pin "4") (pinfunction "SCK_4") (pintype "bidirectional"))
    )
    (net (code "58") (name "SW_3V3_2") (class "Default")
      (node (ref "H1") (pin "2.20") (pinfunction "2.20_2.20") (pintype "bidirectional"))
      (node (ref "R8") (pin "2") (pinfunction "2_2") (pintype "passive"))
    )
    (net (code "59") (name "TX_ON") (class "Default")
      (node (ref "U$1") (pin "31-CTX3") (pinfunction "31-CTX3_31-CTX3") (pintype "bidirectional"))
      (node (ref "U3") (pin "11") (pinfunction "TXON_11") (pintype "bidirectional"))
    )
    (net (code "60") (name "T_CS") (class "Default")
      (node (ref "J4") (pin "1") (pinfunction "1_1") (pintype "passive"))
      (node (ref "U$1") (pin "10-CS\\MQSR") (pinfunction "10-CS/MQSR_10-CS\\MQSR") (pintype "bidirectional"))
    )
    (net (code "61") (name "T_CS1") (class "Default")
      (node (ref "H1") (pin "2.4") (pinfunction "2.4_2.4") (pintype "bidirectional"))
      (node (ref "U$1") (pin "9-OUT1C") (pinfunction "9-OUT1C_9-OUT1C") (pintype "bidirectional"))
    )
    (net (code "62") (name "T_GPIO2") (class "Default")
      (node (ref "J3") (pin "5") (pinfunction "5_5") (pintype "passive"))
      (node (ref "U$1") (pin "2-OUT2") (pinfunction "2-OUT2_2-OUT2") (pintype "bidirectional"))
    )
    (net (code "63") (name "T_GPIO3") (class "Default")
      (node (ref "J3") (pin "4") (pinfunction "4_4") (pintype "passive"))
      (node (ref "U$1") (pin "3-LRCLK2") (pinfunction "3-LRCLK2_3-LRCLK2") (pintype "bidirectional"))
    )
    (net (code "64") (name "T_GPIO4") (class "Default")
      (node (ref "J3") (pin "3") (pinfunction "3_3") (pintype "passive"))
      (node (ref "U$1") (pin "4-BCLK2") (pinfunction "4-BCLK2_4-BCLK2") (pintype "bidirectional"))
    )
    (net (code "65") (name "T_GPIO5") (class "Default")
      (node (ref "J3") (pin "2") (pinfunction "2_2") (pintype "passive"))
      (node (ref "U$1") (pin "5-IN2") (pinfunction "5-IN2_5-IN2") (pintype "bidirectional"))
    )
    (net (code "66") (name "T_GPIO6") (class "Default")
      (node (ref "J3") (pin "1") (pinfunction "1_1") (pintype "passive"))
      (node (ref "U$1") (pin "6-OUT1D") (pinfunction "6-OUT1D_6-OUT1D") (pintype "bidirectional"))
    )
    (net (code "67") (name "T_PROGRAM") (class "Default")
      (node (ref "J11") (pin "2") (pinfunction "2_2") (pintype "passive"))
      (node (ref "U$1") (pin "PROGRAM") (pinfunction "PROGRAM_PROGRAM") (pintype "bidirectional"))
    )
    (net (code "68") (name "T_VBAT") (class "Default")
      (node (ref "J11") (pin "1") (pinfunction "1_1") (pintype "passive"))
      (node (ref "U$1") (pin "VBAT") (pinfunction "VBAT_VBAT") (pintype "bidirectional"))
    )
    (net (code "69") (name "T_VUSB") (class "Default")
      (node (ref "J12") (pin "1") (pinfunction "1_1") (pintype "passive"))
      (node (ref "U$1") (pin "VUSB") (pinfunction "VUSB_VUSB") (pintype "bidirectional"))
    )
    (net (code "70") (name "UART2_RXD") (class "Default")
      (node (ref "J2") (pin "1") (pinfunction "1_1") (pintype "passive"))
      (node (ref "U$1") (pin "34-RX8") (pinfunction "34-RX8_34-RX8") (pintype "bidirectional"))
    )
    (net (code "71") (name "UART2_TXD") (class "Default")
      (node (ref "J2") (pin "3") (pinfunction "3_3") (pintype "passive"))
      (node (ref "U$1") (pin "35-TX8") (pinfunction "35/TX8_35-TX8") (pintype "bidirectional"))
    )
    (net (code "72") (name "UART4_RXD") (class "Default")
      (node (ref "H1") (pin "1.2") (pinfunction "1.2_1.2") (pintype "bidirectional"))
      (node (ref "U$1") (pin "0-RX1/CS1/CRX2") (pinfunction "0-RX1/CS1/CRX2_0-RX1/CS1/CRX2") (pintype "bidirectional"))
    )
    (net (code "73") (name "UART4_TXD") (class "Default")
      (node (ref "H1") (pin "1.1") (pinfunction "1.1_1.1") (pintype "bidirectional"))
      (node (ref "U$1") (pin "1-TX1/MISO1/CTX2") (pinfunction "1-TX1/MISO1/CTX2_1-TX1/MISO1/CTX2") (pintype "bidirectional"))
    )
    (net (code "74") (name "UART5_RXD") (class "Default")
      (node (ref "J14") (pin "3") (pinfunction "3_3") (pintype "passive"))
      (node (ref "U$1") (pin "29-TX7") (pinfunction "29-TX7_29-TX7") (pintype "bidirectional"))
      (node (ref "U6") (pin "42") (pinfunction "GPS_RXDO_42") (pintype "input"))
    )
    (net (code "75") (name "UART5_TXD") (class "Default")
      (node (ref "J14") (pin "4") (pinfunction "4_4") (pintype "passive"))
      (node (ref "U$1") (pin "28-RX7") (pinfunction "28-RX7_28-RX7") (pintype "bidirectional"))
      (node (ref "U6") (pin "44") (pinfunction "GPS_TXD0_44") (pintype "output"))
    )
    (net (code "76") (name "UART6_RX") (class "Default")
      (node (ref "U$1") (pin "7-RX2/OUT1A") (pinfunction "7-RX2/OUT1A_7-RX2/OUT1A") (pintype "bidirectional"))
      (node (ref "X1") (pin "8") (pinfunction "P$8_8") (pintype "bidirectional"))
    )
    (net (code "77") (name "UART6_TX") (class "Default")
      (node (ref "U$1") (pin "8-TX2/IN1") (pinfunction "8-TX2/IN1_8-TX2/IN1") (pintype "bidirectional"))
      (node (ref "X1") (pin "10") (pinfunction "P$10_10") (pintype "bidirectional"))
    )
    (net (code "78") (name "USB_DEV_D+") (class "Default")
      (node (ref "J12") (pin "4") (pinfunction "4_4") (pintype "passive"))
      (node (ref "U$1") (pin "D+") (pinfunction "D+_D+") (pintype "bidirectional"))
    )
    (net (code "79") (name "USB_DEV_D-") (class "Default")
      (node (ref "J12") (pin "3") (pinfunction "3_3") (pintype "passive"))
      (node (ref "U$1") (pin "D-") (pinfunction "D-_D-") (pintype "bidirectional"))
    )
    (net (code "80") (name "USB_HOST_D+") (class "Default")
      (node (ref "J13") (pin "1") (pinfunction "1_1") (pintype "passive"))
      (node (ref "U$1") (pin "DP") (pinfunction "DP_DP") (pintype "bidirectional"))
    )
    (net (code "81") (name "USB_HOST_D-") (class "Default")
      (node (ref "J13") (pin "2") (pinfunction "2_2") (pintype "passive"))
      (node (ref "U$1") (pin "DM") (pinfunction "DM_DM") (pintype "bidirectional"))
    )
    (net (code "82") (name "unconnected-(H1-Pad1.9)") (class "Default")
      (node (ref "H1") (pin "1.9") (pinfunction "1.9_1.9") (pintype "bidirectional"))
    )
    (net (code "83") (name "unconnected-(H1-Pad1.10)") (class "Default")
      (node (ref "H1") (pin "1.10") (pinfunction "1.10_1.10") (pintype "bidirectional"))
    )
    (net (code "84") (name "unconnected-(H1-Pad1.11)") (class "Default")
      (node (ref "H1") (pin "1.11") (pinfunction "1.11_1.11") (pintype "bidirectional"))
    )
    (net (code "85") (name "unconnected-(H1-Pad1.12)") (class "Default")
      (node (ref "H1") (pin "1.12") (pinfunction "1.12_1.12") (pintype "bidirectional"))
    )
    (net (code "86") (name "unconnected-(H1-Pad1.13)") (class "Default")
      (node (ref "H1") (pin "1.13") (pinfunction "1.13_1.13") (pintype "bidirectional"))
    )
    (net (code "87") (name "unconnected-(H1-Pad1.14)") (class "Default")
      (node (ref "H1") (pin "1.14") (pinfunction "1.14_1.14") (pintype "bidirectional"))
    )
    (net (code "88") (name "unconnected-(H1-Pad1.15)") (class "Default")
      (node (ref "H1") (pin "1.15") (pinfunction "1.15_1.15") (pintype "bidirectional"))
    )
    (net (code "89") (name "unconnected-(H1-Pad1.16)") (class "Default")
      (node (ref "H1") (pin "1.16") (pinfunction "1.16_1.16") (pintype "bidirectional"))
    )
    (net (code "90") (name "unconnected-(H1-Pad1.17)") (class "Default")
      (node (ref "H1") (pin "1.17") (pinfunction "1.17_1.17") (pintype "bidirectional"))
    )
    (net (code "91") (name "unconnected-(H1-Pad1.18)") (class "Default")
      (node (ref "H1") (pin "1.18") (pinfunction "1.18_1.18") (pintype "bidirectional"))
    )
    (net (code "92") (name "unconnected-(H1-Pad1.19)") (class "Default")
      (node (ref "H1") (pin "1.19") (pinfunction "1.19_1.19") (pintype "bidirectional"))
    )
    (net (code "93") (name "unconnected-(H1-Pad1.20)") (class "Default")
      (node (ref "H1") (pin "1.20") (pinfunction "1.20_1.20") (pintype "bidirectional"))
    )
    (net (code "94") (name "unconnected-(H1-Pad1.21)") (class "Default")
      (node (ref "H1") (pin "1.21") (pinfunction "1.21_1.21") (pintype "bidirectional"))
    )
    (net (code "95") (name "unconnected-(H1-Pad1.22)") (class "Default")
      (node (ref "H1") (pin "1.22") (pinfunction "1.22_1.22") (pintype "bidirectional"))
    )
    (net (code "96") (name "unconnected-(H1-Pad1.23)") (class "Default")
      (node (ref "H1") (pin "1.23") (pinfunction "1.23_1.23") (pintype "bidirectional"))
    )
    (net (code "97") (name "unconnected-(H1-Pad1.24)") (class "Default")
      (node (ref "H1") (pin "1.24") (pinfunction "1.24_1.24") (pintype "bidirectional"))
    )
    (net (code "98") (name "unconnected-(H1-Pad1.25)") (class "Default")
      (node (ref "H1") (pin "1.25") (pinfunction "1.25_1.25") (pintype "bidirectional"))
    )
    (net (code "99") (name "unconnected-(H1-Pad1.26)") (class "Default")
      (node (ref "H1") (pin "1.26") (pinfunction "1.26_1.26") (pintype "bidirectional"))
    )
    (net (code "100") (name "unconnected-(H1-Pad1.27)") (class "Default")
      (node (ref "H1") (pin "1.27") (pinfunction "1.27_1.27") (pintype "bidirectional"))
    )
    (net (code "101") (name "unconnected-(H1-Pad1.28)") (class "Default")
      (node (ref "H1") (pin "1.28") (pinfunction "1.28_1.28") (pintype "bidirectional"))
    )
    (net (code "102") (name "unconnected-(H1-Pad1.29)") (class "Default")
      (node (ref "H1") (pin "1.29") (pinfunction "1.29_1.29") (pintype "bidirectional"))
    )
    (net (code "103") (name "unconnected-(H1-Pad1.30)") (class "Default")
      (node (ref "H1") (pin "1.30") (pinfunction "1.30_1.30") (pintype "bidirectional"))
    )
    (net (code "104") (name "unconnected-(H1-Pad1.31)") (class "Default")
      (node (ref "H1") (pin "1.31") (pinfunction "1.31_1.31") (pintype "bidirectional"))
    )
    (net (code "105") (name "unconnected-(H1-Pad1.32)") (class "Default")
      (node (ref "H1") (pin "1.32") (pinfunction "1.32_1.32") (pintype "bidirectional"))
    )
    (net (code "106") (name "unconnected-(H1-Pad1.33)") (class "Default")
      (node (ref "H1") (pin "1.33") (pinfunction "1.33_1.33") (pintype "bidirectional"))
    )
    (net (code "107") (name "unconnected-(H1-Pad1.34)") (class "Default")
      (node (ref "H1") (pin "1.34") (pinfunction "1.34_1.34") (pintype "bidirectional"))
    )
    (net (code "108") (name "unconnected-(H1-Pad1.35)") (class "Default")
      (node (ref "H1") (pin "1.35") (pinfunction "1.35_1.35") (pintype "bidirectional"))
    )
    (net (code "109") (name "unconnected-(H1-Pad1.36)") (class "Default")
      (node (ref "H1") (pin "1.36") (pinfunction "1.36_1.36") (pintype "bidirectional"))
    )
    (net (code "110") (name "unconnected-(H1-Pad1.37)") (class "Default")
      (node (ref "H1") (pin "1.37") (pinfunction "1.37_1.37") (pintype "bidirectional"))
    )
    (net (code "111") (name "unconnected-(H1-Pad1.38)") (class "Default")
      (node (ref "H1") (pin "1.38") (pinfunction "1.38_1.38") (pintype "bidirectional"))
    )
    (net (code "112") (name "unconnected-(H1-Pad1.39)") (class "Default")
      (node (ref "H1") (pin "1.39") (pinfunction "1.39_1.39") (pintype "bidirectional"))
    )
    (net (code "113") (name "unconnected-(H1-Pad1.40)") (class "Default")
      (node (ref "H1") (pin "1.40") (pinfunction "1.40_1.40") (pintype "bidirectional"))
    )
    (net (code "114") (name "unconnected-(H1-Pad1.42)") (class "Default")
      (node (ref "H1") (pin "1.42") (pinfunction "1.42_1.42") (pintype "bidirectional"))
    )
    (net (code "115") (name "unconnected-(H1-Pad1.44)") (class "Default")
      (node (ref "H1") (pin "1.44") (pinfunction "1.44_1.44") (pintype "bidirectional"))
    )
    (net (code "116") (name "unconnected-(H1-Pad1.45)") (class "Default")
      (node (ref "H1") (pin "1.45") (pinfunction "1.45_1.45") (pintype "bidirectional"))
    )
    (net (code "117") (name "unconnected-(H1-Pad1.46)") (class "Default")
      (node (ref "H1") (pin "1.46") (pinfunction "1.46_1.46") (pintype "bidirectional"))
    )
    (net (code "118") (name "unconnected-(H1-Pad1.47)") (class "Default")
      (node (ref "H1") (pin "1.47") (pinfunction "1.47_1.47") (pintype "bidirectional"))
    )
    (net (code "119") (name "unconnected-(H1-Pad1.48)") (class "Default")
      (node (ref "H1") (pin "1.48") (pinfunction "1.48_1.48") (pintype "bidirectional"))
    )
    (net (code "120") (name "unconnected-(H1-Pad1.49)") (class "Default")
      (node (ref "H1") (pin "1.49") (pinfunction "1.49_1.49") (pintype "bidirectional"))
    )
    (net (code "121") (name "unconnected-(H1-Pad1.50)") (class "Default")
      (node (ref "H1") (pin "1.50") (pinfunction "1.50_1.50") (pintype "bidirectional"))
    )
    (net (code "122") (name "unconnected-(H1-Pad1.51)") (class "Default")
      (node (ref "H1") (pin "1.51") (pinfunction "1.51_1.51") (pintype "bidirectional"))
    )
    (net (code "123") (name "unconnected-(H1-Pad1.52)") (class "Default")
      (node (ref "H1") (pin "1.52") (pinfunction "1.52_1.52") (pintype "bidirectional"))
    )
    (net (code "124") (name "unconnected-(H1-Pad2.5)") (class "Default")
      (node (ref "H1") (pin "2.5") (pinfunction "2.5_2.5") (pintype "bidirectional"))
    )
    (net (code "125") (name "unconnected-(H1-Pad2.6)") (class "Default")
      (node (ref "H1") (pin "2.6") (pinfunction "2.6_2.6") (pintype "bidirectional"))
    )
    (net (code "126") (name "unconnected-(H1-Pad2.8)") (class "Default")
      (node (ref "H1") (pin "2.8") (pinfunction "2.8_2.8") (pintype "bidirectional"))
    )
    (net (code "127") (name "unconnected-(H1-Pad2.9)") (class "Default")
      (node (ref "H1") (pin "2.9") (pinfunction "2.9_2.9") (pintype "bidirectional"))
    )
    (net (code "128") (name "unconnected-(H1-Pad2.10)") (class "Default")
      (node (ref "H1") (pin "2.10") (pinfunction "2.10_2.10") (pintype "bidirectional"))
    )
    (net (code "129") (name "unconnected-(H1-Pad2.11)") (class "Default")
      (node (ref "H1") (pin "2.11") (pinfunction "2.11_2.11") (pintype "bidirectional"))
    )
    (net (code "130") (name "unconnected-(H1-Pad2.12)") (class "Default")
      (node (ref "H1") (pin "2.12") (pinfunction "2.12_2.12") (pintype "bidirectional"))
    )
    (net (code "131") (name "unconnected-(H1-Pad2.13)") (class "Default")
      (node (ref "H1") (pin "2.13") (pinfunction "2.13_2.13") (pintype "bidirectional"))
    )
    (net (code "132") (name "unconnected-(H1-Pad2.15)") (class "Default")
      (node (ref "H1") (pin "2.15") (pinfunction "2.15_2.15") (pintype "bidirectional"))
    )
    (net (code "133") (name "unconnected-(H1-Pad2.16)") (class "Default")
      (node (ref "H1") (pin "2.16") (pinfunction "2.16_2.16") (pintype "bidirectional"))
    )
    (net (code "134") (name "unconnected-(H1-Pad2.18)") (class "Default")
      (node (ref "H1") (pin "2.18") (pinfunction "2.18_2.18") (pintype "bidirectional"))
    )
    (net (code "135") (name "unconnected-(H1-Pad2.19)") (class "Default")
      (node (ref "H1") (pin "2.19") (pinfunction "2.19_2.19") (pintype "bidirectional"))
    )
    (net (code "136") (name "unconnected-(H1-Pad2.23)") (class "Default")
      (node (ref "H1") (pin "2.23") (pinfunction "2.23_2.23") (pintype "bidirectional"))
    )
    (net (code "137") (name "unconnected-(H1-Pad2.24)") (class "Default")
      (node (ref "H1") (pin "2.24") (pinfunction "2.24_2.24") (pintype "bidirectional"))
    )
    (net (code "138") (name "unconnected-(H1-Pad2.31)") (class "Default")
      (node (ref "H1") (pin "2.31") (pinfunction "2.31_2.31") (pintype "bidirectional"))
    )
    (net (code "139") (name "unconnected-(H1-Pad2.33)") (class "Default")
      (node (ref "H1") (pin "2.33") (pinfunction "2.33_2.33") (pintype "bidirectional"))
    )
    (net (code "140") (name "unconnected-(H1-Pad2.34)") (class "Default")
      (node (ref "H1") (pin "2.34") (pinfunction "2.34_2.34") (pintype "bidirectional"))
    )
    (net (code "141") (name "unconnected-(H1-Pad2.35)") (class "Default")
      (node (ref "H1") (pin "2.35") (pinfunction "2.35_2.35") (pintype "bidirectional"))
    )
    (net (code "142") (name "unconnected-(H1-Pad2.36)") (class "Default")
      (node (ref "H1") (pin "2.36") (pinfunction "2.36_2.36") (pintype "bidirectional"))
    )
    (net (code "143") (name "unconnected-(H1-Pad2.37)") (class "Default")
      (node (ref "H1") (pin "2.37") (pinfunction "2.37_2.37") (pintype "bidirectional"))
    )
    (net (code "144") (name "unconnected-(H1-Pad2.38)") (class "Default")
      (node (ref "H1") (pin "2.38") (pinfunction "2.38_2.38") (pintype "bidirectional"))
    )
    (net (code "145") (name "unconnected-(H1-Pad2.39)") (class "Default")
      (node (ref "H1") (pin "2.39") (pinfunction "2.39_2.39") (pintype "bidirectional"))
    )
    (net (code "146") (name "unconnected-(H1-Pad2.40)") (class "Default")
      (node (ref "H1") (pin "2.40") (pinfunction "2.40_2.40") (pintype "bidirectional"))
    )
    (net (code "147") (name "unconnected-(H1-Pad2.41)") (class "Default")
      (node (ref "H1") (pin "2.41") (pinfunction "2.41_2.41") (pintype "bidirectional"))
    )
    (net (code "148") (name "unconnected-(H1-Pad2.42)") (class "Default")
      (node (ref "H1") (pin "2.42") (pinfunction "2.42_2.42") (pintype "bidirectional"))
    )
    (net (code "149") (name "unconnected-(H1-Pad2.43)") (class "Default")
      (node (ref "H1") (pin "2.43") (pinfunction "2.43_2.43") (pintype "bidirectional"))
    )
    (net (code "150") (name "unconnected-(H1-Pad2.44)") (class "Default")
      (node (ref "H1") (pin "2.44") (pinfunction "2.44_2.44") (pintype "bidirectional"))
    )
    (net (code "151") (name "unconnected-(H1-Pad2.45)") (class "Default")
      (node (ref "H1") (pin "2.45") (pinfunction "2.45_2.45") (pintype "bidirectional"))
    )
    (net (code "152") (name "unconnected-(H1-Pad2.46)") (class "Default")
      (node (ref "H1") (pin "2.46") (pinfunction "2.46_2.46") (pintype "bidirectional"))
    )
    (net (code "153") (name "unconnected-(H1-Pad2.49)") (class "Default")
      (node (ref "H1") (pin "2.49") (pinfunction "2.49_2.49") (pintype "bidirectional"))
    )
    (net (code "154") (name "unconnected-(H1-Pad2.50)") (class "Default")
      (node (ref "H1") (pin "2.50") (pinfunction "2.50_2.50") (pintype "bidirectional"))
    )
    (net (code "155") (name "unconnected-(H1-Pad2.51)") (class "Default")
      (node (ref "H1") (pin "2.51") (pinfunction "2.51_2.51") (pintype "bidirectional"))
    )
    (net (code "156") (name "unconnected-(H1-Pad2.52)") (class "Default")
      (node (ref "H1") (pin "2.52") (pinfunction "2.52_2.52") (pintype "bidirectional"))
    )
    (net (code "157") (name "unconnected-(H1-PadP$1)") (class "Default")
      (node (ref "H1") (pin "P$1") (pinfunction "P$1_P$1") (pintype "bidirectional"))
    )
    (net (code "158") (name "unconnected-(H1-PadP$2)") (class "Default")
      (node (ref "H1") (pin "P$2") (pinfunction "P$2_P$2") (pintype "bidirectional"))
    )
    (net (code "159") (name "unconnected-(H1-PadP$3)") (class "Default")
      (node (ref "H1") (pin "P$3") (pinfunction "P$3_P$3") (pintype "bidirectional"))
    )
    (net (code "160") (name "unconnected-(U$1-PadON{slash}OFF)") (class "Default")
      (node (ref "U$1") (pin "ON/OFF") (pinfunction "ON/OFF_ON/OFF") (pintype "bidirectional"))
    )
    (net (code "161") (name "unconnected-(U1-NC-Pad7)") (class "Default")
      (node (ref "U1") (pin "7") (pinfunction "NC_7") (pintype "no_connect"))
    )
    (net (code "162") (name "unconnected-(U1-NC_2-Pad2)") (class "Default")
      (node (ref "U1") (pin "2") (pinfunction "NC_2_2") (pintype "no_connect"))
    )
    (net (code "163") (name "unconnected-(U1-NC_3-Pad3)") (class "Default")
      (node (ref "U1") (pin "3") (pinfunction "NC_3_3") (pintype "no_connect"))
    )
    (net (code "164") (name "unconnected-(U1-NC_4-Pad6)") (class "Default")
      (node (ref "U1") (pin "6") (pinfunction "NC_4_6") (pintype "no_connect"))
    )
    (net (code "165") (name "unconnected-(U3-GPIO_2-Pad16)") (class "Default")
      (node (ref "U3") (pin "16") (pinfunction "GPIO_2_16") (pintype "bidirectional"))
    )
    (net (code "166") (name "unconnected-(U4-DIO0-Pad14)") (class "Default")
      (node (ref "U4") (pin "14") (pinfunction "DIO0_14") (pintype "bidirectional"))
    )
    (net (code "167") (name "unconnected-(U4-DIO2-Pad16)") (class "Default")
      (node (ref "U4") (pin "16") (pinfunction "DIO2_16") (pintype "bidirectional"))
    )
    (net (code "168") (name "unconnected-(U4-DIO3-Pad11)") (class "Default")
      (node (ref "U4") (pin "11") (pinfunction "DIO3_11") (pintype "bidirectional"))
    )
    (net (code "169") (name "unconnected-(U4-DIO4-Pad12)") (class "Default")
      (node (ref "U4") (pin "12") (pinfunction "DIO4_12") (pintype "bidirectional"))
    )
    (net (code "170") (name "unconnected-(U4-DIO5-Pad7)") (class "Default")
      (node (ref "U4") (pin "7") (pinfunction "DIO5_7") (pintype "bidirectional"))
    )
    (net (code "171") (name "unconnected-(U5-Pad1)") (class "Default")
      (node (ref "U5") (pin "1") (pinfunction "1_1") (pintype "passive"))
    )
    (net (code "172") (name "unconnected-(U6-P$3-Pad3)") (class "Default")
      (node (ref "U6") (pin "3") (pinfunction "P$3_3") (pintype "bidirectional"))
    )
    (net (code "173") (name "unconnected-(U6-P$4-Pad4)") (class "Default")
      (node (ref "U6") (pin "4") (pinfunction "P$4_4") (pintype "bidirectional"))
    )
    (net (code "174") (name "unconnected-(U6-P$5-Pad5)") (class "Default")
      (node (ref "U6") (pin "5") (pinfunction "P$5_5") (pintype "bidirectional"))
    )
    (net (code "175") (name "unconnected-(U6-P$6-Pad6)") (class "Default")
      (node (ref "U6") (pin "6") (pinfunction "P$6_6") (pintype "bidirectional"))
    )
    (net (code "176") (name "unconnected-(U6-P$8-Pad8)") (class "Default")
      (node (ref "U6") (pin "8") (pinfunction "P$8_8") (pintype "bidirectional"))
    )
    (net (code "177") (name "unconnected-(U6-P$12-Pad12)") (class "Default")
      (node (ref "U6") (pin "12") (pinfunction "P$12_12") (pintype "bidirectional"))
    )
    (net (code "178") (name "unconnected-(U6-P$13-Pad13)") (class "Default")
      (node (ref "U6") (pin "13") (pinfunction "P$13_13") (pintype "bidirectional"))
    )
    (net (code "179") (name "unconnected-(U6-P$14-Pad14)") (class "Default")
      (node (ref "U6") (pin "14") (pinfunction "P$14_14") (pintype "bidirectional"))
    )
    (net (code "180") (name "unconnected-(U6-P$16-Pad16)") (class "Default")
      (node (ref "U6") (pin "16") (pinfunction "P$16_16") (pintype "bidirectional"))
    )
    (net (code "181") (name "unconnected-(U6-P$17-Pad17)") (class "Default")
      (node (ref "U6") (pin "17") (pinfunction "P$17_17") (pintype "bidirectional"))
    )
    (net (code "182") (name "unconnected-(U6-P$20-Pad20)") (class "Default")
      (node (ref "U6") (pin "20") (pinfunction "P$20_20") (pintype "bidirectional"))
    )
    (net (code "183") (name "unconnected-(U6-P$23-Pad23)") (class "Default")
      (node (ref "U6") (pin "23") (pinfunction "P$23_23") (pintype "bidirectional"))
    )
    (net (code "184") (name "unconnected-(U6-P$26-Pad26)") (class "Default")
      (node (ref "U6") (pin "26") (pinfunction "P$26_26") (pintype "bidirectional"))
    )
    (net (code "185") (name "unconnected-(U6-P$30-Pad30)") (class "Default")
      (node (ref "U6") (pin "30") (pinfunction "P$30_30") (pintype "bidirectional"))
    )
    (net (code "186") (name "unconnected-(U6-P$34-Pad34)") (class "Default")
      (node (ref "U6") (pin "34") (pinfunction "P$34_34") (pintype "bidirectional"))
    )
    (net (code "187") (name "unconnected-(U6-P$35-Pad35)") (class "Default")
      (node (ref "U6") (pin "35") (pinfunction "P$35_35") (pintype "bidirectional"))
    )
    (net (code "188") (name "unconnected-(U6-P$36-Pad36)") (class "Default")
      (node (ref "U6") (pin "36") (pinfunction "P$36_36") (pintype "bidirectional"))
    )
    (net (code "189") (name "unconnected-(U6-P$37-Pad37)") (class "Default")
      (node (ref "U6") (pin "37") (pinfunction "P$37_37") (pintype "bidirectional"))
    )
    (net (code "190") (name "unconnected-(U6-P$38-Pad38)") (class "Default")
      (node (ref "U6") (pin "38") (pinfunction "P$38_38") (pintype "bidirectional"))
    )
    (net (code "191") (name "unconnected-(U6-P$39-Pad39)") (class "Default")
      (node (ref "U6") (pin "39") (pinfunction "P$39_39") (pintype "bidirectional"))
    )
    (net (code "192") (name "unconnected-(U6-P$40-Pad40)") (class "Default")
      (node (ref "U6") (pin "40") (pinfunction "P$40_40") (pintype "bidirectional"))
    )
    (net (code "193") (name "unconnected-(U6-P$41-Pad41)") (class "Default")
      (node (ref "U6") (pin "41") (pinfunction "P$41_41") (pintype "bidirectional"))
    )
    (net (code "194") (name "unconnected-(U6-P$43-Pad43)") (class "Default")
      (node (ref "U6") (pin "43") (pinfunction "P$43_43") (pintype "bidirectional"))
    )
    (net (code "195") (name "unconnected-(U6-P$45-Pad45)") (class "Default")
      (node (ref "U6") (pin "45") (pinfunction "P$45_45") (pintype "bidirectional"))
    )
    (net (code "196") (name "unconnected-(U6-P$46-Pad46)") (class "Default")
      (node (ref "U6") (pin "46") (pinfunction "P$46_46") (pintype "bidirectional"))
    )
    (net (code "197") (name "unconnected-(U6-P$47-Pad47)") (class "Default")
      (node (ref "U6") (pin "47") (pinfunction "P$47_47") (pintype "bidirectional"))
    )
    (net (code "198") (name "unconnected-(U6-P$48-Pad48)") (class "Default")
      (node (ref "U6") (pin "48") (pinfunction "P$48_48") (pintype "bidirectional"))
    )
    (net (code "199") (name "unconnected-(U6-P$49-Pad49)") (class "Default")
      (node (ref "U6") (pin "49") (pinfunction "P$49_49") (pintype "bidirectional"))
    )
    (net (code "200") (name "unconnected-(U6-P$50-Pad50)") (class "Default")
      (node (ref "U6") (pin "50") (pinfunction "P$50_50") (pintype "bidirectional"))
    )
    (net (code "201") (name "unconnected-(U6-P$51-Pad51)") (class "Default")
      (node (ref "U6") (pin "51") (pinfunction "P$51_51") (pintype "bidirectional"))
    )
    (net (code "202") (name "unconnected-(U6-P$52-Pad52)") (class "Default")
      (node (ref "U6") (pin "52") (pinfunction "P$52_52") (pintype "bidirectional"))
    )
    (net (code "203") (name "unconnected-(U6-P$53-Pad53)") (class "Default")
      (node (ref "U6") (pin "53") (pinfunction "P$53_53") (pintype "bidirectional"))
    )
    (net (code "204") (name "unconnected-(U6-P$54-Pad54)") (class "Default")
      (node (ref "U6") (pin "54") (pinfunction "P$54_54") (pintype "bidirectional"))
    )
    (net (code "205") (name "unconnected-(U6-P$55-Pad55)") (class "Default")
      (node (ref "U6") (pin "55") (pinfunction "P$55_55") (pintype "bidirectional"))
    )
    (net (code "206") (name "unconnected-(U6-P$56-Pad56)") (class "Default")
      (node (ref "U6") (pin "56") (pinfunction "P$56_56") (pintype "bidirectional"))
    )
    (net (code "207") (name "unconnected-(U6-P$57-Pad57)") (class "Default")
      (node (ref "U6") (pin "57") (pinfunction "P$57_57") (pintype "bidirectional"))
    )
    (net (code "208") (name "unconnected-(U6-P$59-Pad59)") (class "Default")
      (node (ref "U6") (pin "59") (pinfunction "P$59_59") (pintype "bidirectional"))
    )
    (net (code "209") (name "unconnected-(U6-P$60-Pad60)") (class "Default")
      (node (ref "U6") (pin "60") (pinfunction "P$60_60") (pintype "bidirectional"))
    )
    (net (code "210") (name "unconnected-(U6-P$61-Pad61)") (class "Default")
      (node (ref "U6") (pin "61") (pinfunction "P$61_61") (pintype "bidirectional"))
    )
    (net (code "211") (name "unconnected-(U6-P$62-Pad62)") (class "Default")
      (node (ref "U6") (pin "62") (pinfunction "P$62_62") (pintype "bidirectional"))
    )
    (net (code "212") (name "unconnected-(U6-P$63-Pad63)") (class "Default")
      (node (ref "U6") (pin "63") (pinfunction "P$63_63") (pintype "bidirectional"))
    )
    (net (code "213") (name "unconnected-(U6-P$65-Pad65)") (class "Default")
      (node (ref "U6") (pin "65") (pinfunction "P$65_65") (pintype "bidirectional"))
    )
    (net (code "214") (name "unconnected-(U6-P$66-Pad66)") (class "Default")
      (node (ref "U6") (pin "66") (pinfunction "P$66_66") (pintype "bidirectional"))
    )
    (net (code "215") (name "unconnected-(U6-P$67-Pad67)") (class "Default")
      (node (ref "U6") (pin "67") (pinfunction "P$67_67") (pintype "bidirectional"))
    )
    (net (code "216") (name "unconnected-(U6-P$68-Pad68)") (class "Default")
      (node (ref "U6") (pin "68") (pinfunction "P$68_68") (pintype "bidirectional"))
    )
    (net (code "217") (name "unconnected-(U6-P$69-Pad69)") (class "Default")
      (node (ref "U6") (pin "69") (pinfunction "P$69_69") (pintype "bidirectional"))
    )
    (net (code "218") (name "unconnected-(X1-P$1-Pad1)") (class "Default")
      (node (ref "X1") (pin "1") (pinfunction "P$1_1") (pintype "bidirectional"))
    )
    (net (code "219") (name "unconnected-(X1-P$4-Pad4)") (class "Default")
      (node (ref "X1") (pin "4") (pinfunction "P$4_4") (pintype "bidirectional"))
    )
    (net (code "220") (name "unconnected-(X1-P$6-Pad6)") (class "Default")
      (node (ref "X1") (pin "6") (pinfunction "P$6_6") (pintype "bidirectional"))
    )
    (net (code "221") (name "unconnected-(X1-P$7-Pad7)") (class "Default")
      (node (ref "X1") (pin "7") (pinfunction "P$7_7") (pintype "bidirectional"))
    )
    (net (code "222") (name "unconnected-(X1-P$9-Pad9)") (class "Default")
      (node (ref "X1") (pin "9") (pinfunction "P$9_9") (pintype "bidirectional"))
    )
    (net (code "223") (name "unconnected-(X1-P$12-Pad12)") (class "Default")
      (node (ref "X1") (pin "12") (pinfunction "P$12_12") (pintype "bidirectional"))
    )
    (net (code "224") (name "unconnected-(X1-P$14-Pad14)") (class "Default")
      (node (ref "X1") (pin "14") (pinfunction "P$14_14") (pintype "bidirectional"))
    )
    (net (code "225") (name "unconnected-(X1-P$17-Pad17)") (class "Default")
      (node (ref "X1") (pin "17") (pinfunction "P$17_17") (pintype "bidirectional"))
    )
    (net (code "226") (name "unconnected-(X1-P$20-Pad20)") (class "Default")
      (node (ref "X1") (pin "20") (pinfunction "P$20_20") (pintype "bidirectional"))
    )
    (net (code "227") (name "unconnected-(X1-P$25-Pad25)") (class "Default")
      (node (ref "X1") (pin "25") (pinfunction "P$25_25") (pintype "bidirectional"))
    )
    (net (code "228") (name "unconnected-(X1-P$27-Pad27)") (class "Default")
      (node (ref "X1") (pin "27") (pinfunction "P$27_27") (pintype "bidirectional"))
    )
    (net (code "229") (name "unconnected-(X1-P$28-Pad28)") (class "Default")
      (node (ref "X1") (pin "28") (pinfunction "P$28_28") (pintype "bidirectional"))
    )
    (net (code "230") (name "unconnected-(X1-P$29-Pad29)") (class "Default")
      (node (ref "X1") (pin "29") (pinfunction "P$29_29") (pintype "bidirectional"))
    )
    (net (code "231") (name "unconnected-(X1-P$30-Pad30)") (class "Default")
      (node (ref "X1") (pin "30") (pinfunction "P$30_30") (pintype "bidirectional"))
    )
    (net (code "232") (name "unconnected-(X1-P$31-Pad31)") (class "Default")
      (node (ref "X1") (pin "31") (pinfunction "P$31_31") (pintype "bidirectional"))
    )
    (net (code "233") (name "unconnected-(X1-P$32-Pad32)") (class "Default")
      (node (ref "X1") (pin "32") (pinfunction "P$32_32") (pintype "bidirectional"))
    )
    (net (code "234") (name "unconnected-(X1-P$33-Pad33)") (class "Default")
      (node (ref "X1") (pin "33") (pinfunction "P$33_33") (pintype "bidirectional"))
    )
    (net (code "235") (name "unconnected-(X1-P$34-Pad34)") (class "Default")
      (node (ref "X1") (pin "34") (pinfunction "P$34_34") (pintype "bidirectional"))
    )
    (net (code "236") (name "unconnected-(X1-P$35-Pad35)") (class "Default")
      (node (ref "X1") (pin "35") (pinfunction "P$35_35") (pintype "bidirectional"))
    )
    (net (code "237") (name "unconnected-(X1-P$36-Pad36)") (class "Default")
      (node (ref "X1") (pin "36") (pinfunction "P$36_36") (pintype "bidirectional"))
    )
    (net (code "238") (name "unconnected-(X1-P$37-Pad37)") (class "Default")
      (node (ref "X1") (pin "37") (pinfunction "P$37_37") (pintype "bidirectional"))
    )
    (net (code "239") (name "unconnected-(X1-P$38-Pad38)") (class "Default")
      (node (ref "X1") (pin "38") (pinfunction "P$38_38") (pintype "bidirectional"))
    )
    (net (code "240") (name "unconnected-(X1-P$40-Pad40)") (class "Default")
      (node (ref "X1") (pin "40") (pinfunction "P$40_40") (pintype "bidirectional"))
    )
    (net (code "241") (name "unconnected-(X2-Pad1)") (class "Default")
      (node (ref "X2") (pin "1") (pinfunction "1_1") (pintype "passive"))
    )
    (net (code "242") (name "unconnected-(X2AA-1-Pad33)") (class "Default")
      (node (ref "X2") (pin "33") (pinfunction "1_33") (pintype "passive"))
    )
    (net (code "243") (name "unconnected-(X2AB-1-Pad34)") (class "Default")
      (node (ref "X2") (pin "34") (pinfunction "1_34") (pintype "passive"))
    )
    (net (code "244") (name "unconnected-(X2AC-1-Pad35)") (class "Default")
      (node (ref "X2") (pin "35") (pinfunction "1_35") (pintype "passive"))
    )
    (net (code "245") (name "unconnected-(X2AD-1-Pad36)") (class "Default")
      (node (ref "X2") (pin "36") (pinfunction "1_36") (pintype "passive"))
    )
    (net (code "246") (name "unconnected-(X2AE-1-Pad37)") (class "Default")
      (node (ref "X2") (pin "37") (pinfunction "1_37") (pintype "passive"))
    )
    (net (code "247") (name "unconnected-(X2AF-1-Pad38)") (class "Default")
      (node (ref "X2") (pin "38") (pinfunction "1_38") (pintype "passive"))
    )
    (net (code "248") (name "unconnected-(X2AG-1-Pad39)") (class "Default")
      (node (ref "X2") (pin "39") (pinfunction "1_39") (pintype "passive"))
    )
    (net (code "249") (name "unconnected-(X2AH-1-Pad4)") (class "Default")
      (node (ref "X2") (pin "4") (pinfunction "1_4") (pintype "passive"))
    )
    (net (code "250") (name "unconnected-(X2AI-1-Pad40)") (class "Default")
      (node (ref "X2") (pin "40") (pinfunction "1_40") (pintype "passive"))
    )
    (net (code "251") (name "unconnected-(X2AJ-1-Pad5)") (class "Default")
      (node (ref "X2") (pin "5") (pinfunction "1_5") (pintype "passive"))
    )
    (net (code "252") (name "unconnected-(X2AK-1-Pad6)") (class "Default")
      (node (ref "X2") (pin "6") (pinfunction "1_6") (pintype "passive"))
    )
    (net (code "253") (name "unconnected-(X2AL-1-Pad7)") (class "Default")
      (node (ref "X2") (pin "7") (pinfunction "1_7") (pintype "passive"))
    )
    (net (code "254") (name "unconnected-(X2AM-1-Pad8)") (class "Default")
      (node (ref "X2") (pin "8") (pinfunction "1_8") (pintype "passive"))
    )
    (net (code "255") (name "unconnected-(X2AN-1-Pad9)") (class "Default")
      (node (ref "X2") (pin "9") (pinfunction "1_9") (pintype "passive"))
    )
    (net (code "256") (name "unconnected-(X2B-1-Pad10)") (class "Default")
      (node (ref "X2") (pin "10") (pinfunction "1_10") (pintype "passive"))
    )
    (net (code "257") (name "unconnected-(X2C-1-Pad11)") (class "Default")
      (node (ref "X2") (pin "11") (pinfunction "1_11") (pintype "passive"))
    )
    (net (code "258") (name "unconnected-(X2D-1-Pad12)") (class "Default")
      (node (ref "X2") (pin "12") (pinfunction "1_12") (pintype "passive"))
    )
    (net (code "259") (name "unconnected-(X2E-1-Pad13)") (class "Default")
      (node (ref "X2") (pin "13") (pinfunction "1_13") (pintype "passive"))
    )
    (net (code "260") (name "unconnected-(X2F-1-Pad14)") (class "Default")
      (node (ref "X2") (pin "14") (pinfunction "1_14") (pintype "passive"))
    )
    (net (code "261") (name "unconnected-(X2G-1-Pad15)") (class "Default")
      (node (ref "X2") (pin "15") (pinfunction "1_15") (pintype "passive"))
    )
    (net (code "262") (name "unconnected-(X2H-1-Pad16)") (class "Default")
      (node (ref "X2") (pin "16") (pinfunction "1_16") (pintype "passive"))
    )
    (net (code "263") (name "unconnected-(X2I-1-Pad17)") (class "Default")
      (node (ref "X2") (pin "17") (pinfunction "1_17") (pintype "passive"))
    )
    (net (code "264") (name "unconnected-(X2J-1-Pad18)") (class "Default")
      (node (ref "X2") (pin "18") (pinfunction "1_18") (pintype "passive"))
    )
    (net (code "265") (name "unconnected-(X2K-1-Pad19)") (class "Default")
      (node (ref "X2") (pin "19") (pinfunction "1_19") (pintype "passive"))
    )
    (net (code "266") (name "unconnected-(X2L-1-Pad2)") (class "Default")
      (node (ref "X2") (pin "2") (pinfunction "1_2") (pintype "passive"))
    )
    (net (code "267") (name "unconnected-(X2M-1-Pad20)") (class "Default")
      (node (ref "X2") (pin "20") (pinfunction "1_20") (pintype "passive"))
    )
    (net (code "268") (name "unconnected-(X2N-1-Pad21)") (class "Default")
      (node (ref "X2") (pin "21") (pinfunction "1_21") (pintype "passive"))
    )
    (net (code "269") (name "unconnected-(X2O-1-Pad22)") (class "Default")
      (node (ref "X2") (pin "22") (pinfunction "1_22") (pintype "passive"))
    )
    (net (code "270") (name "unconnected-(X2P-1-Pad23)") (class "Default")
      (node (ref "X2") (pin "23") (pinfunction "1_23") (pintype "passive"))
    )
    (net (code "271") (name "unconnected-(X2Q-1-Pad24)") (class "Default")
      (node (ref "X2") (pin "24") (pinfunction "1_24") (pintype "passive"))
    )
    (net (code "272") (name "unconnected-(X2R-1-Pad25)") (class "Default")
      (node (ref "X2") (pin "25") (pinfunction "1_25") (pintype "passive"))
    )
    (net (code "273") (name "unconnected-(X2S-1-Pad26)") (class "Default")
      (node (ref "X2") (pin "26") (pinfunction "1_26") (pintype "passive"))
    )
    (net (code "274") (name "unconnected-(X2T-1-Pad27)") (class "Default")
      (node (ref "X2") (pin "27") (pinfunction "1_27") (pintype "passive"))
    )
    (net (code "275") (name "unconnected-(X2U-1-Pad28)") (class "Default")
      (node (ref "X2") (pin "28") (pinfunction "1_28") (pintype "passive"))
    )
    (net (code "276") (name "unconnected-(X2V-1-Pad29)") (class "Default")
      (node (ref "X2") (pin "29") (pinfunction "1_29") (pintype "passive"))
    )
    (net (code "277") (name "unconnected-(X2W-1-Pad3)") (class "Default")
      (node (ref "X2") (pin "3") (pinfunction "1_3") (pintype "passive"))
    )
    (net (code "278") (name "unconnected-(X2X-1-Pad30)") (class "Default")
      (node (ref "X2") (pin "30") (pinfunction "1_30") (pintype "passive"))
    )
    (net (code "279") (name "unconnected-(X2Y-1-Pad31)") (class "Default")
      (node (ref "X2") (pin "31") (pinfunction "1_31") (pintype "passive"))
    )
    (net (code "280") (name "unconnected-(X2Z-1-Pad32)") (class "Default")
      (node (ref "X2") (pin "32") (pinfunction "1_32") (pintype "passive"))
    )
  )
)
